# Sheet1.net
KiCad netlist of a schematic drawn in Altium Designer
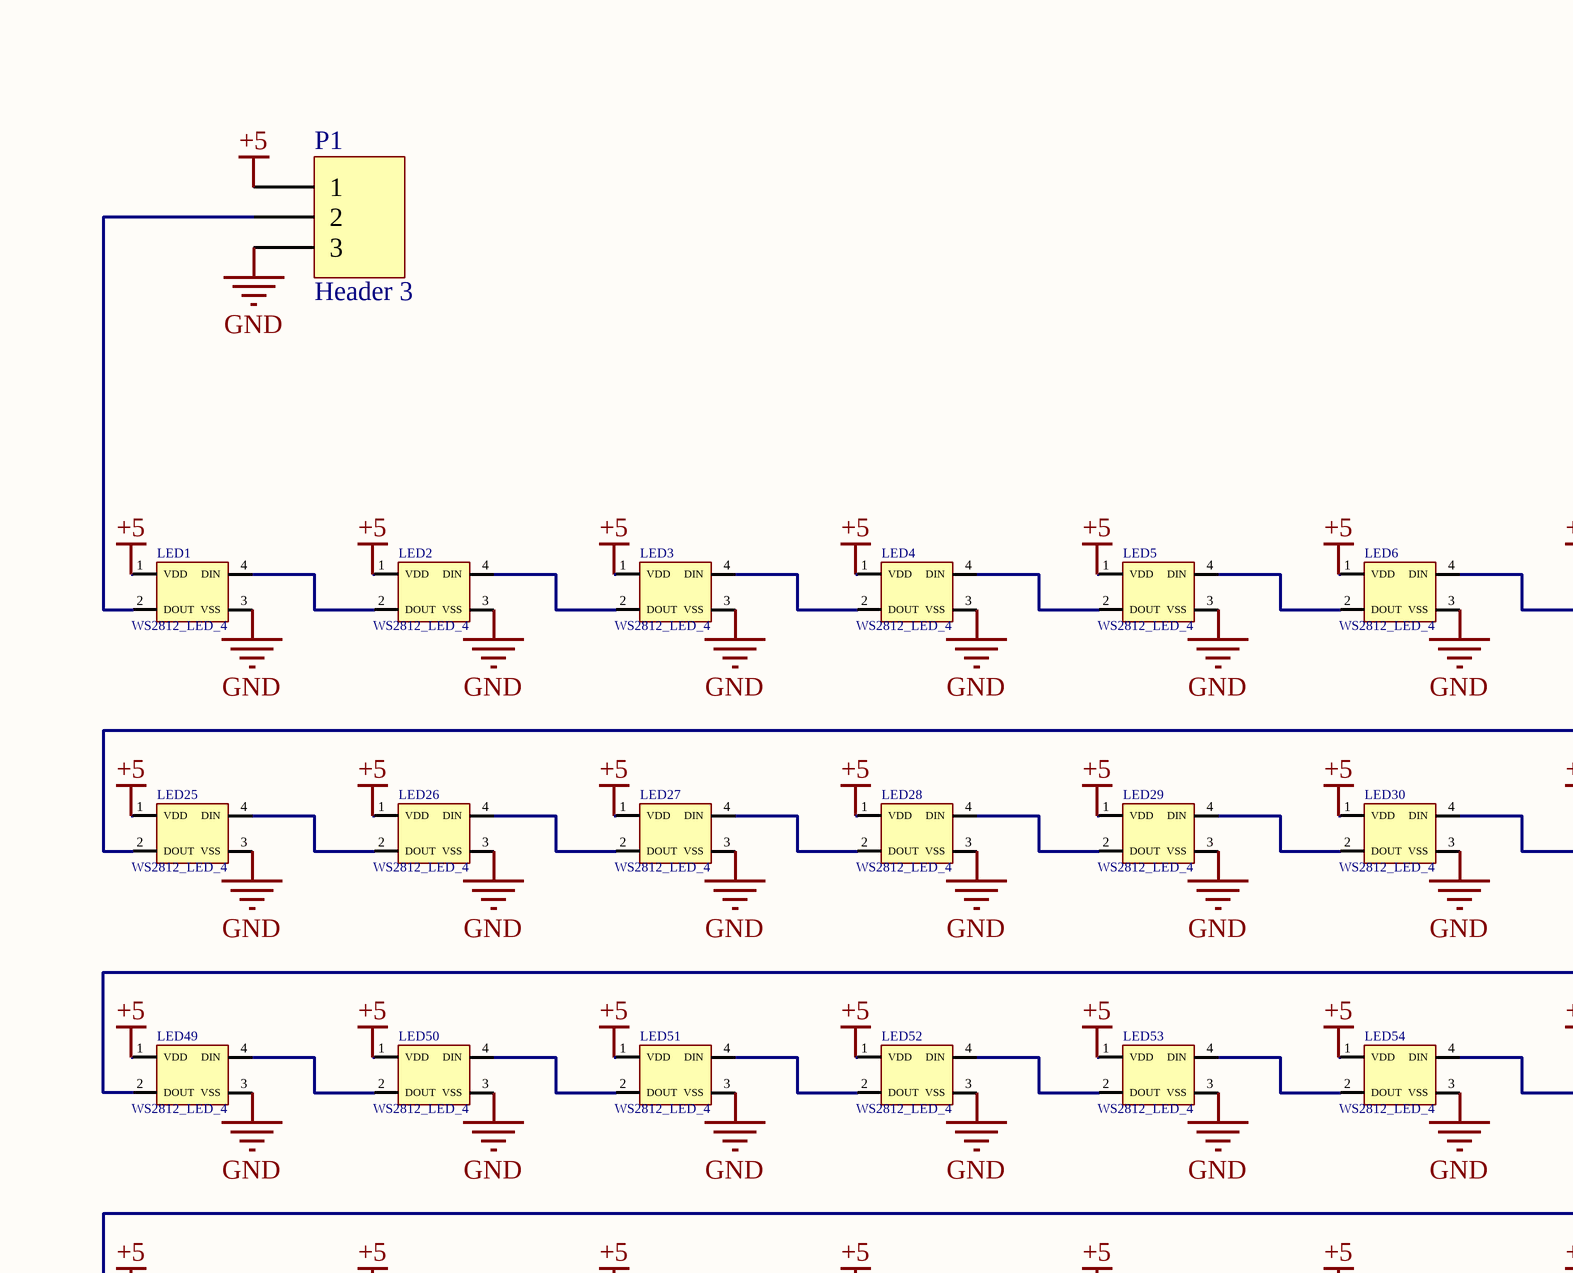
[diagram p0: Sheet1.SchDoc, top column 1 of 4]
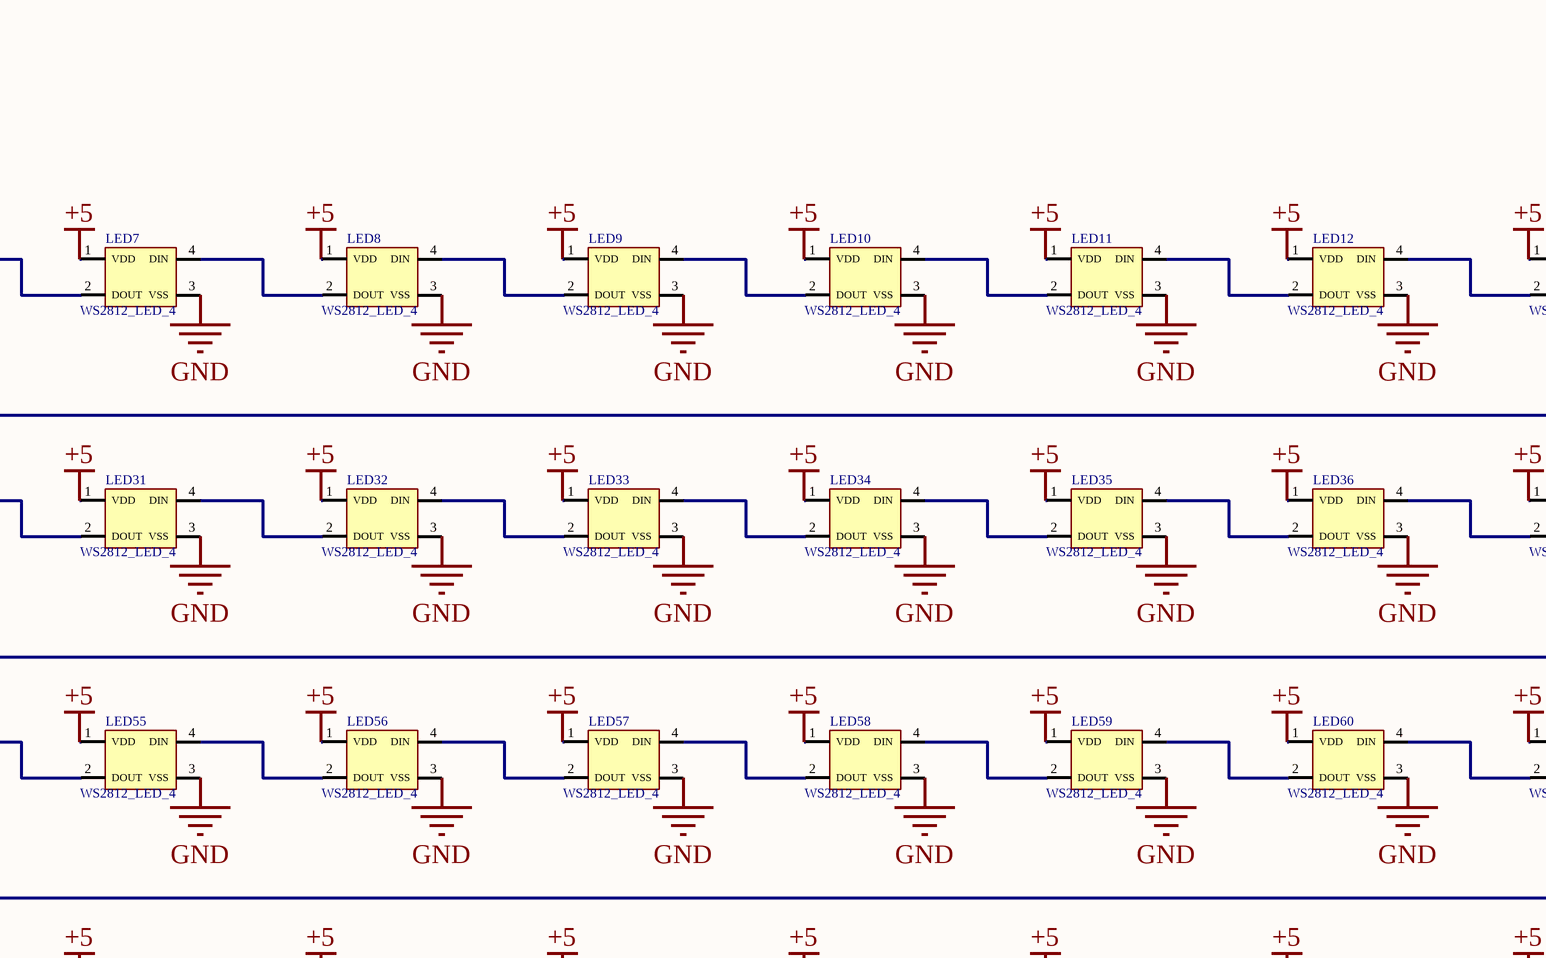
[diagram p1: Sheet1.SchDoc, top column 2 of 4]
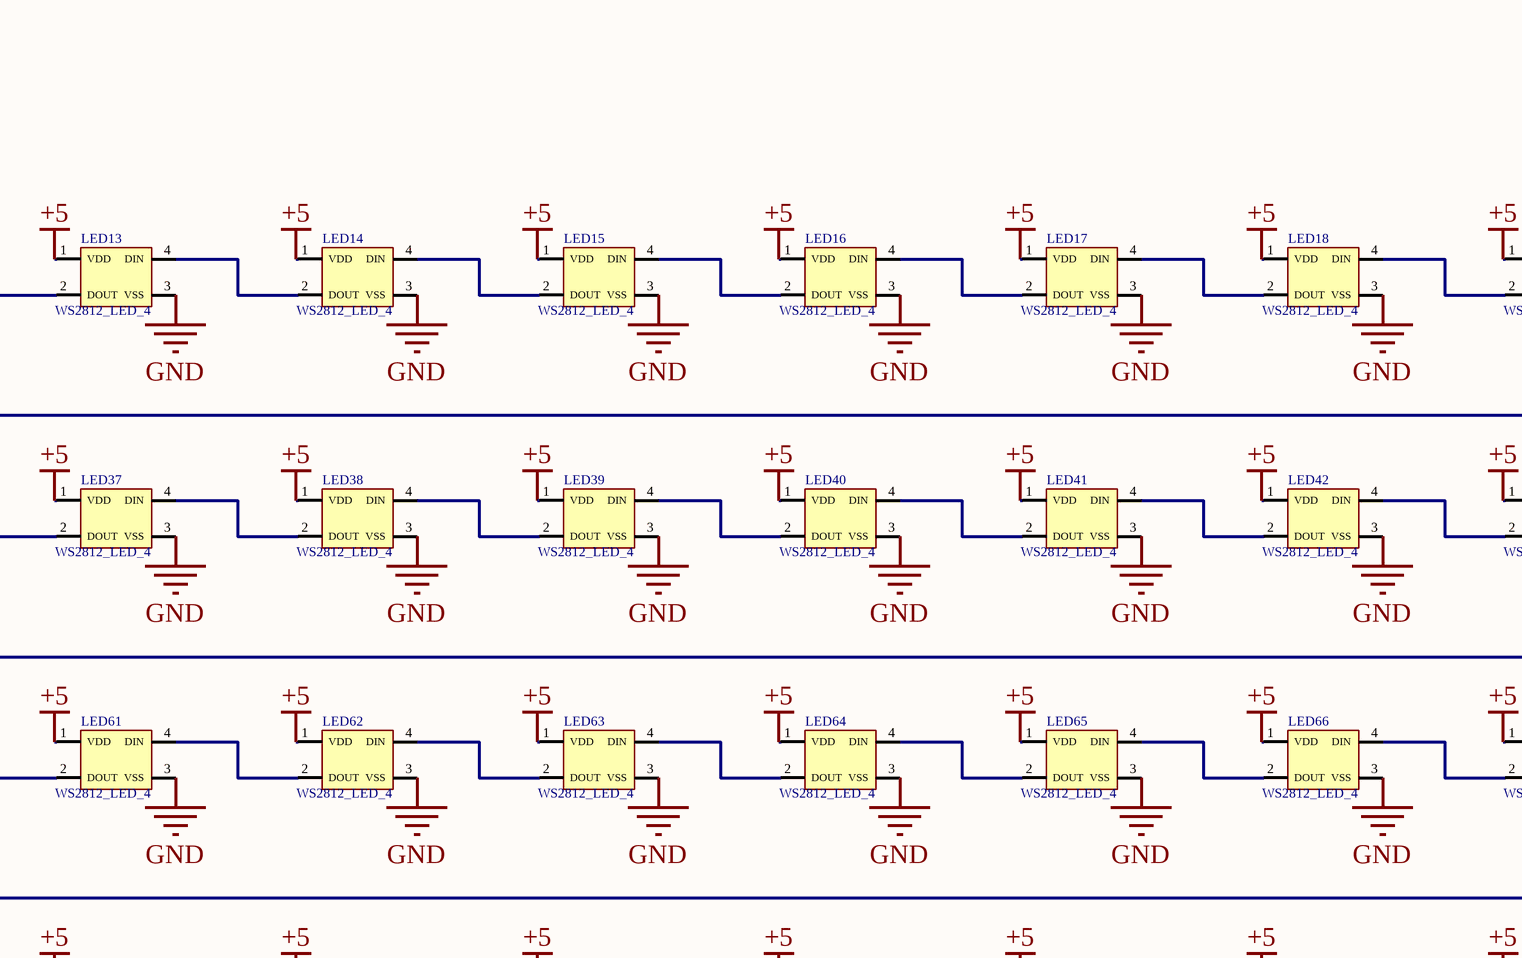
[diagram p2: Sheet1.SchDoc, top column 3 of 4]
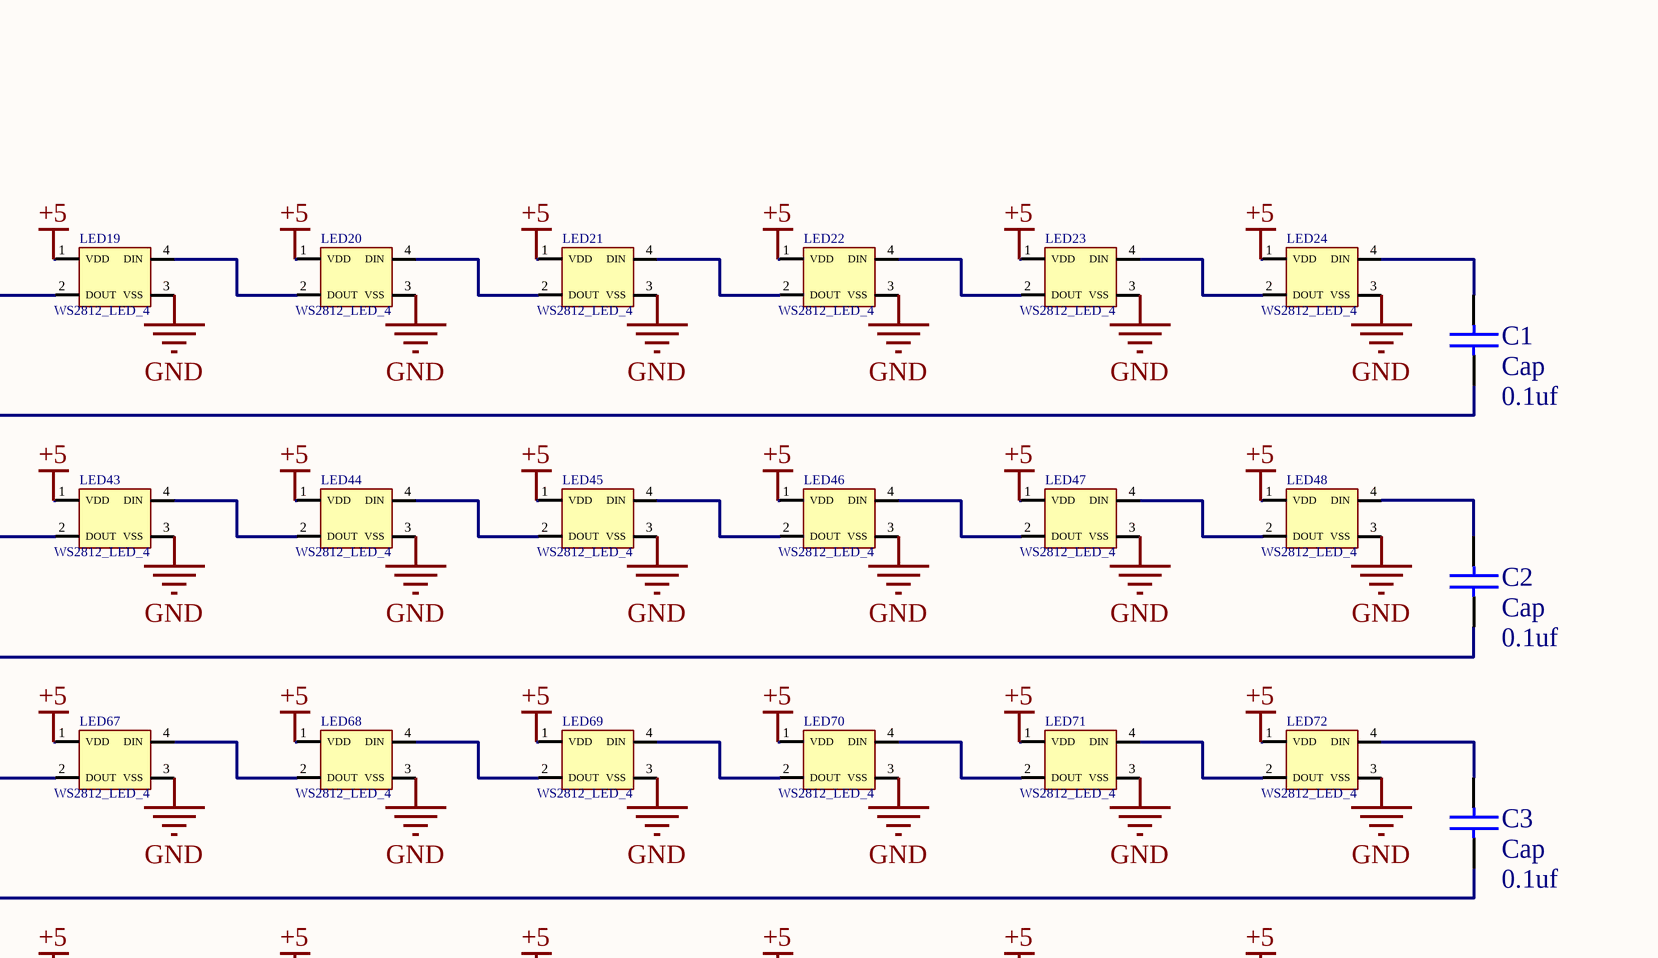
[diagram p3: Sheet1.SchDoc, top column 4 of 4]
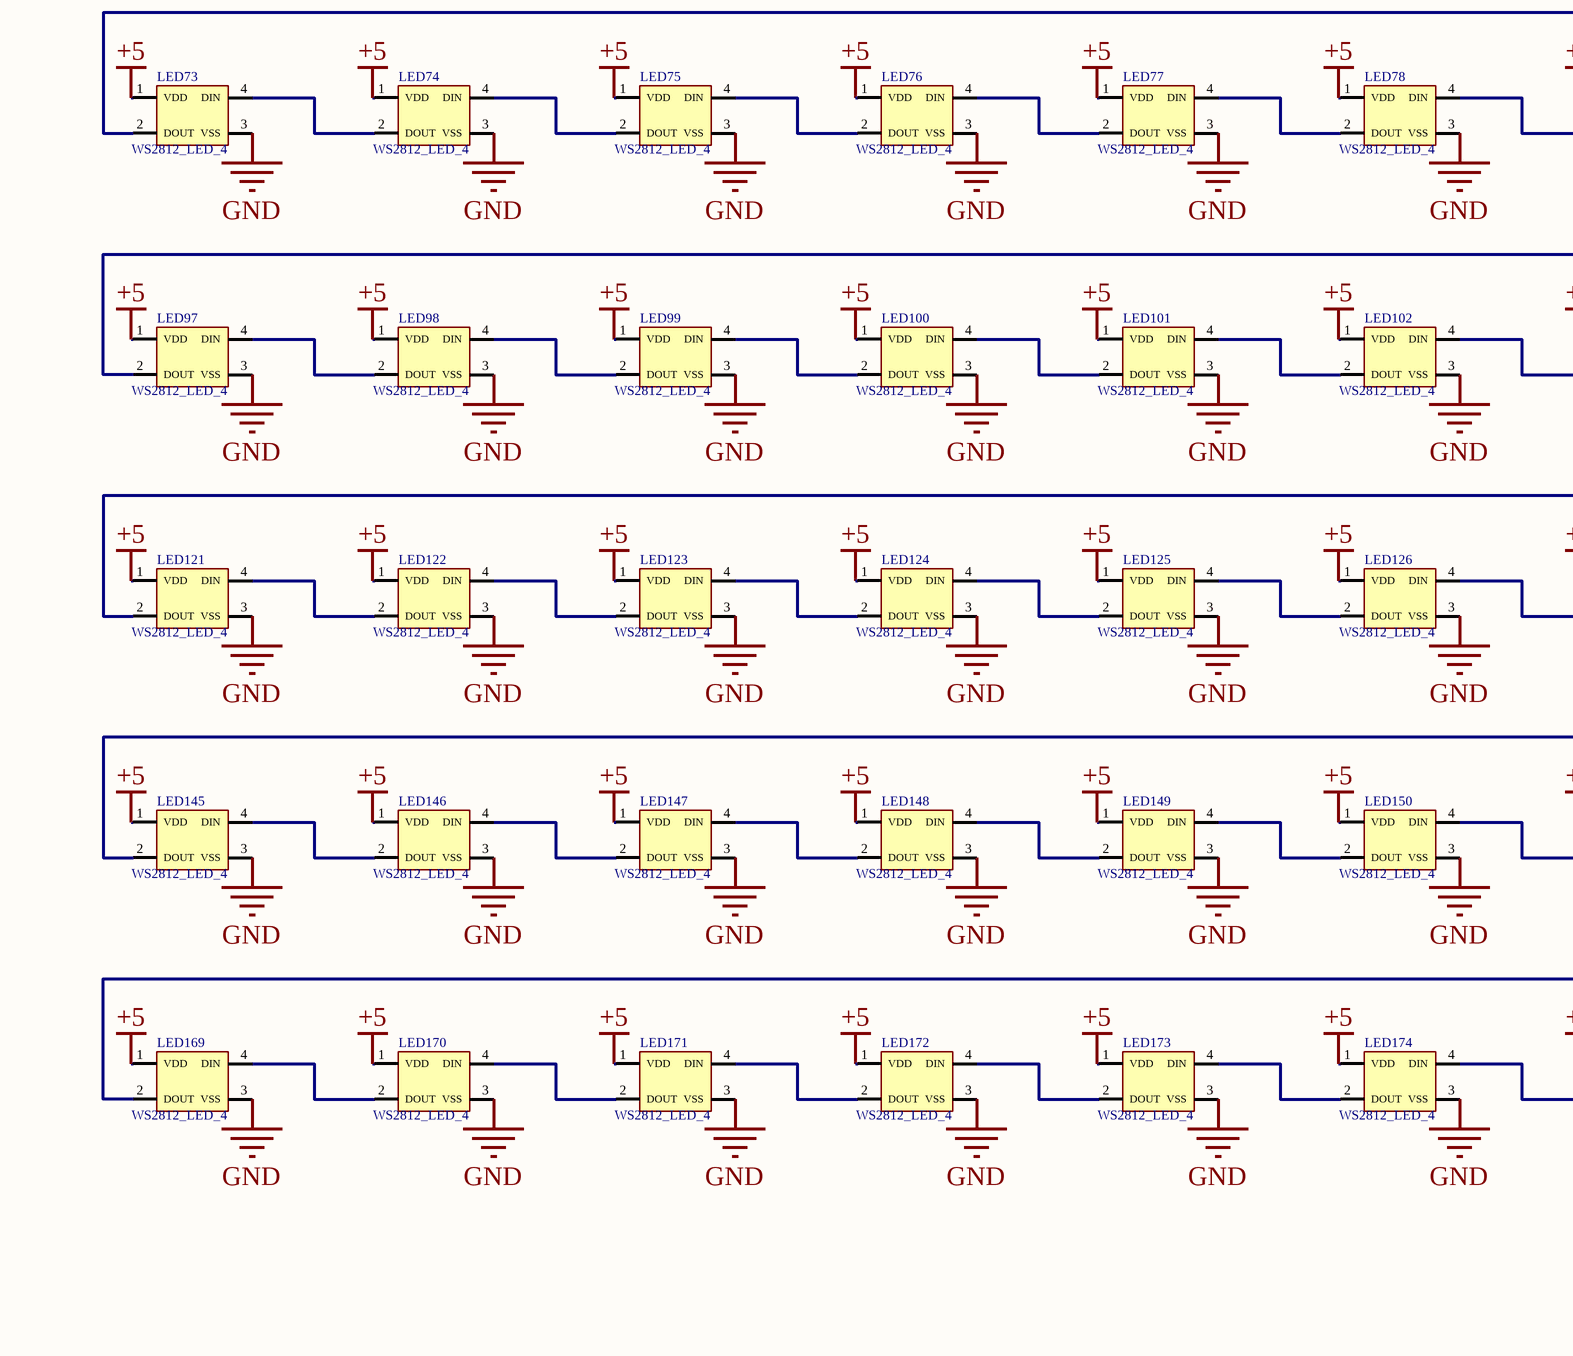
[diagram p4: Sheet1.SchDoc, bottom column 1 of 4]
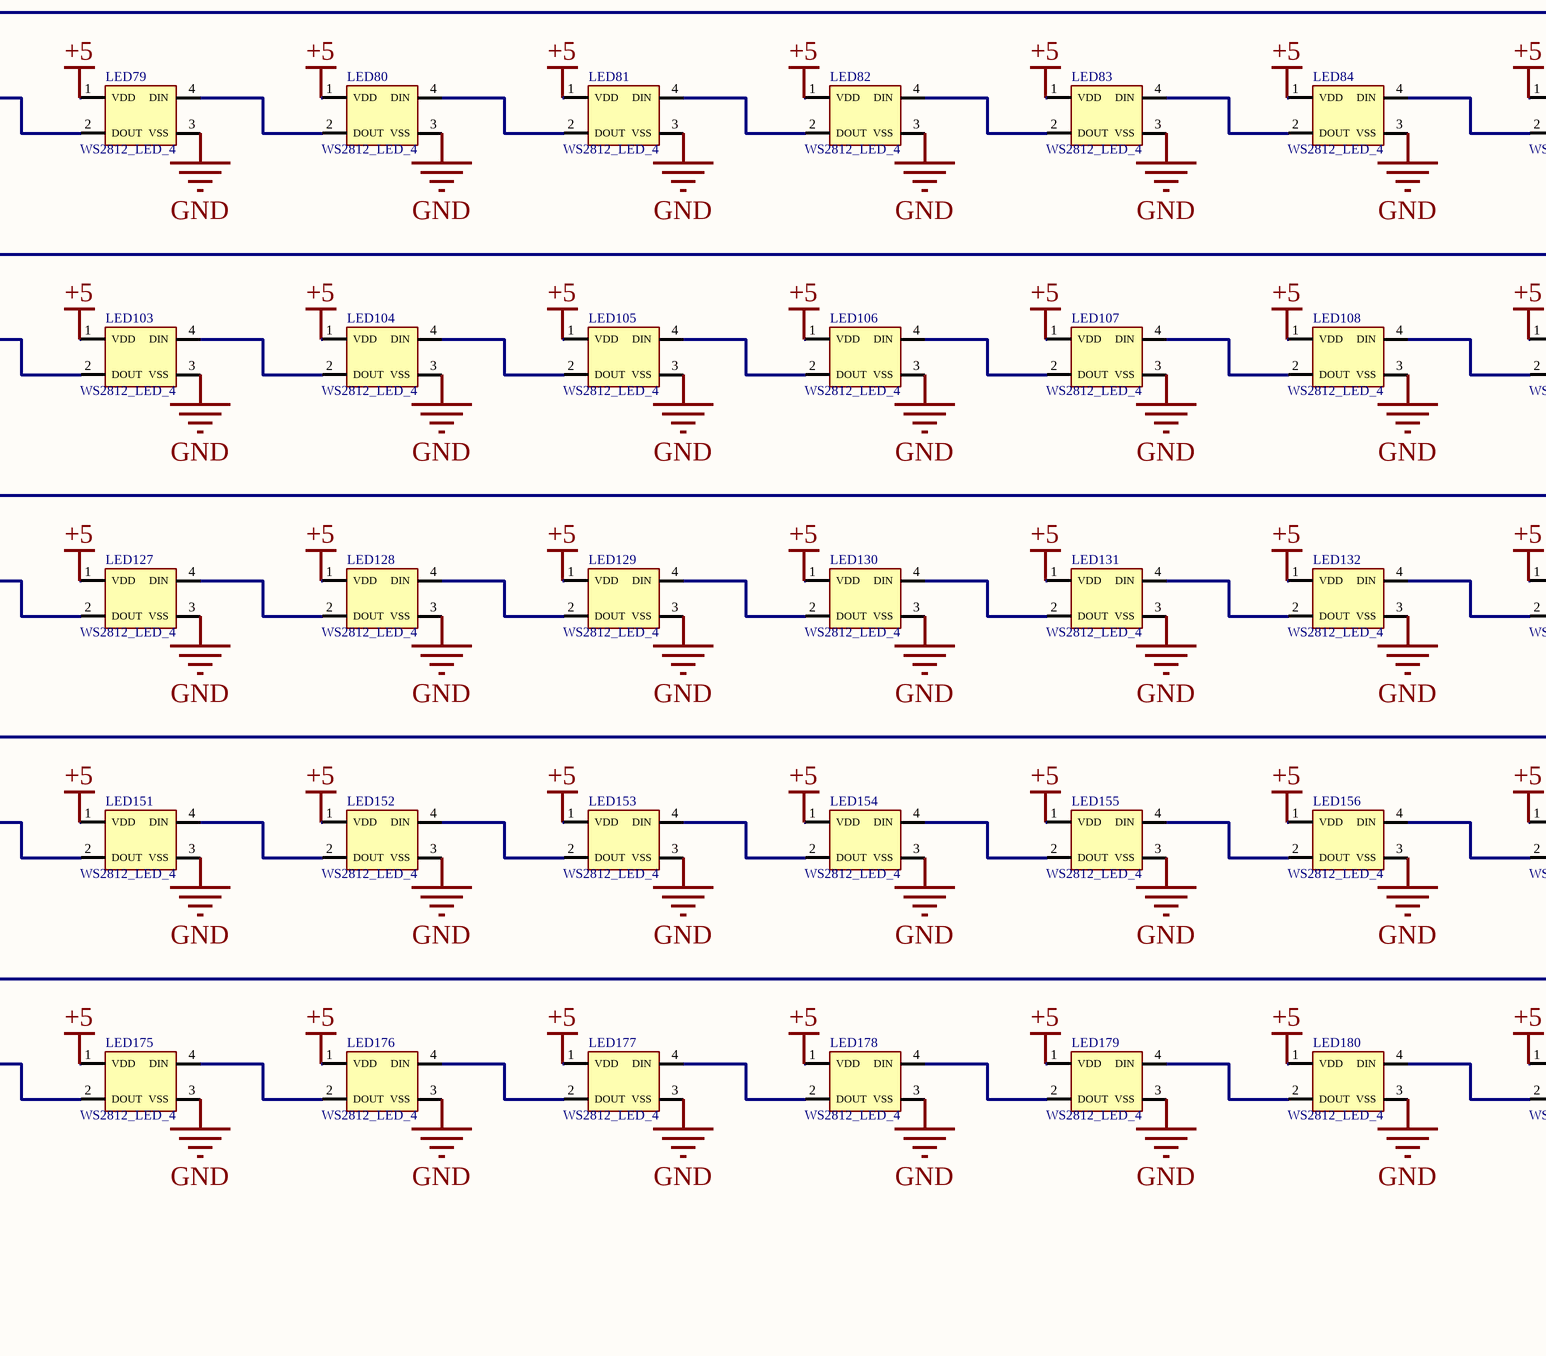
[diagram p5: Sheet1.SchDoc, bottom column 2 of 4]
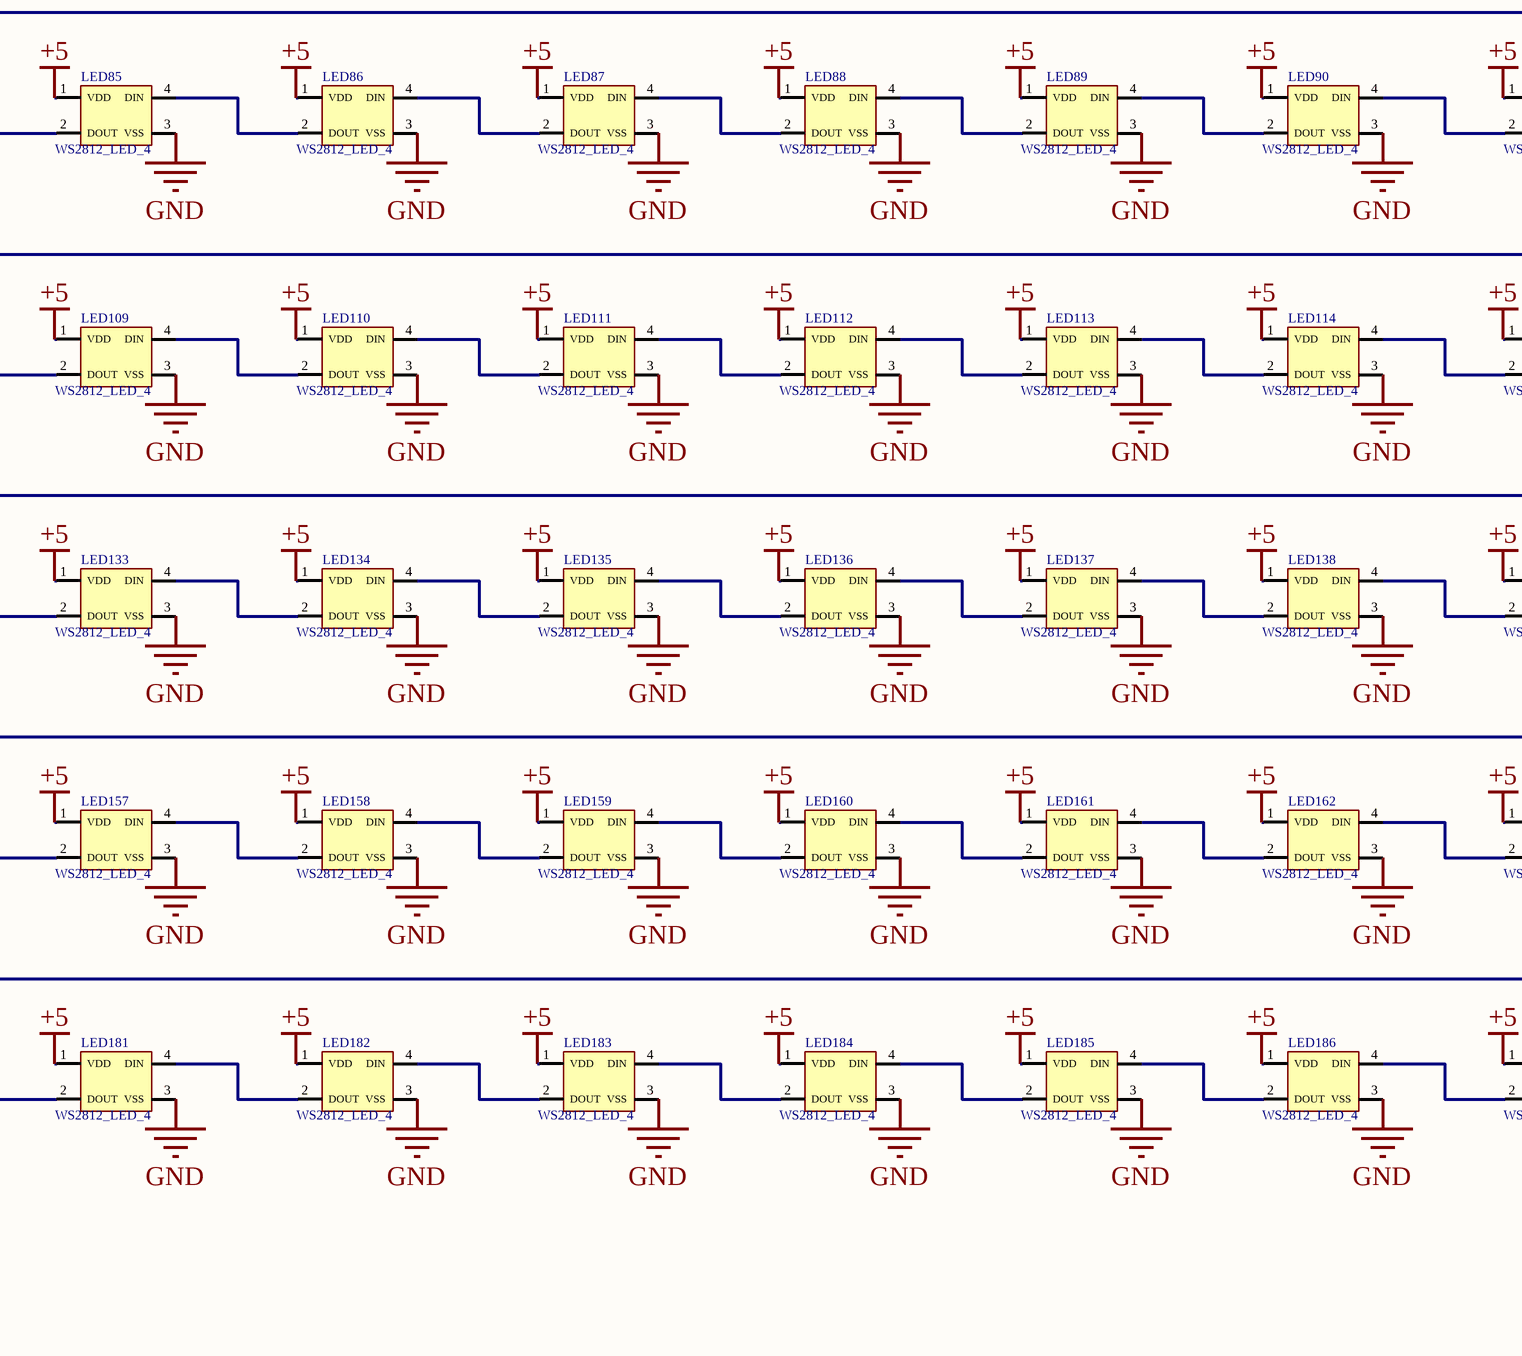
[diagram p6: Sheet1.SchDoc, bottom column 3 of 4]
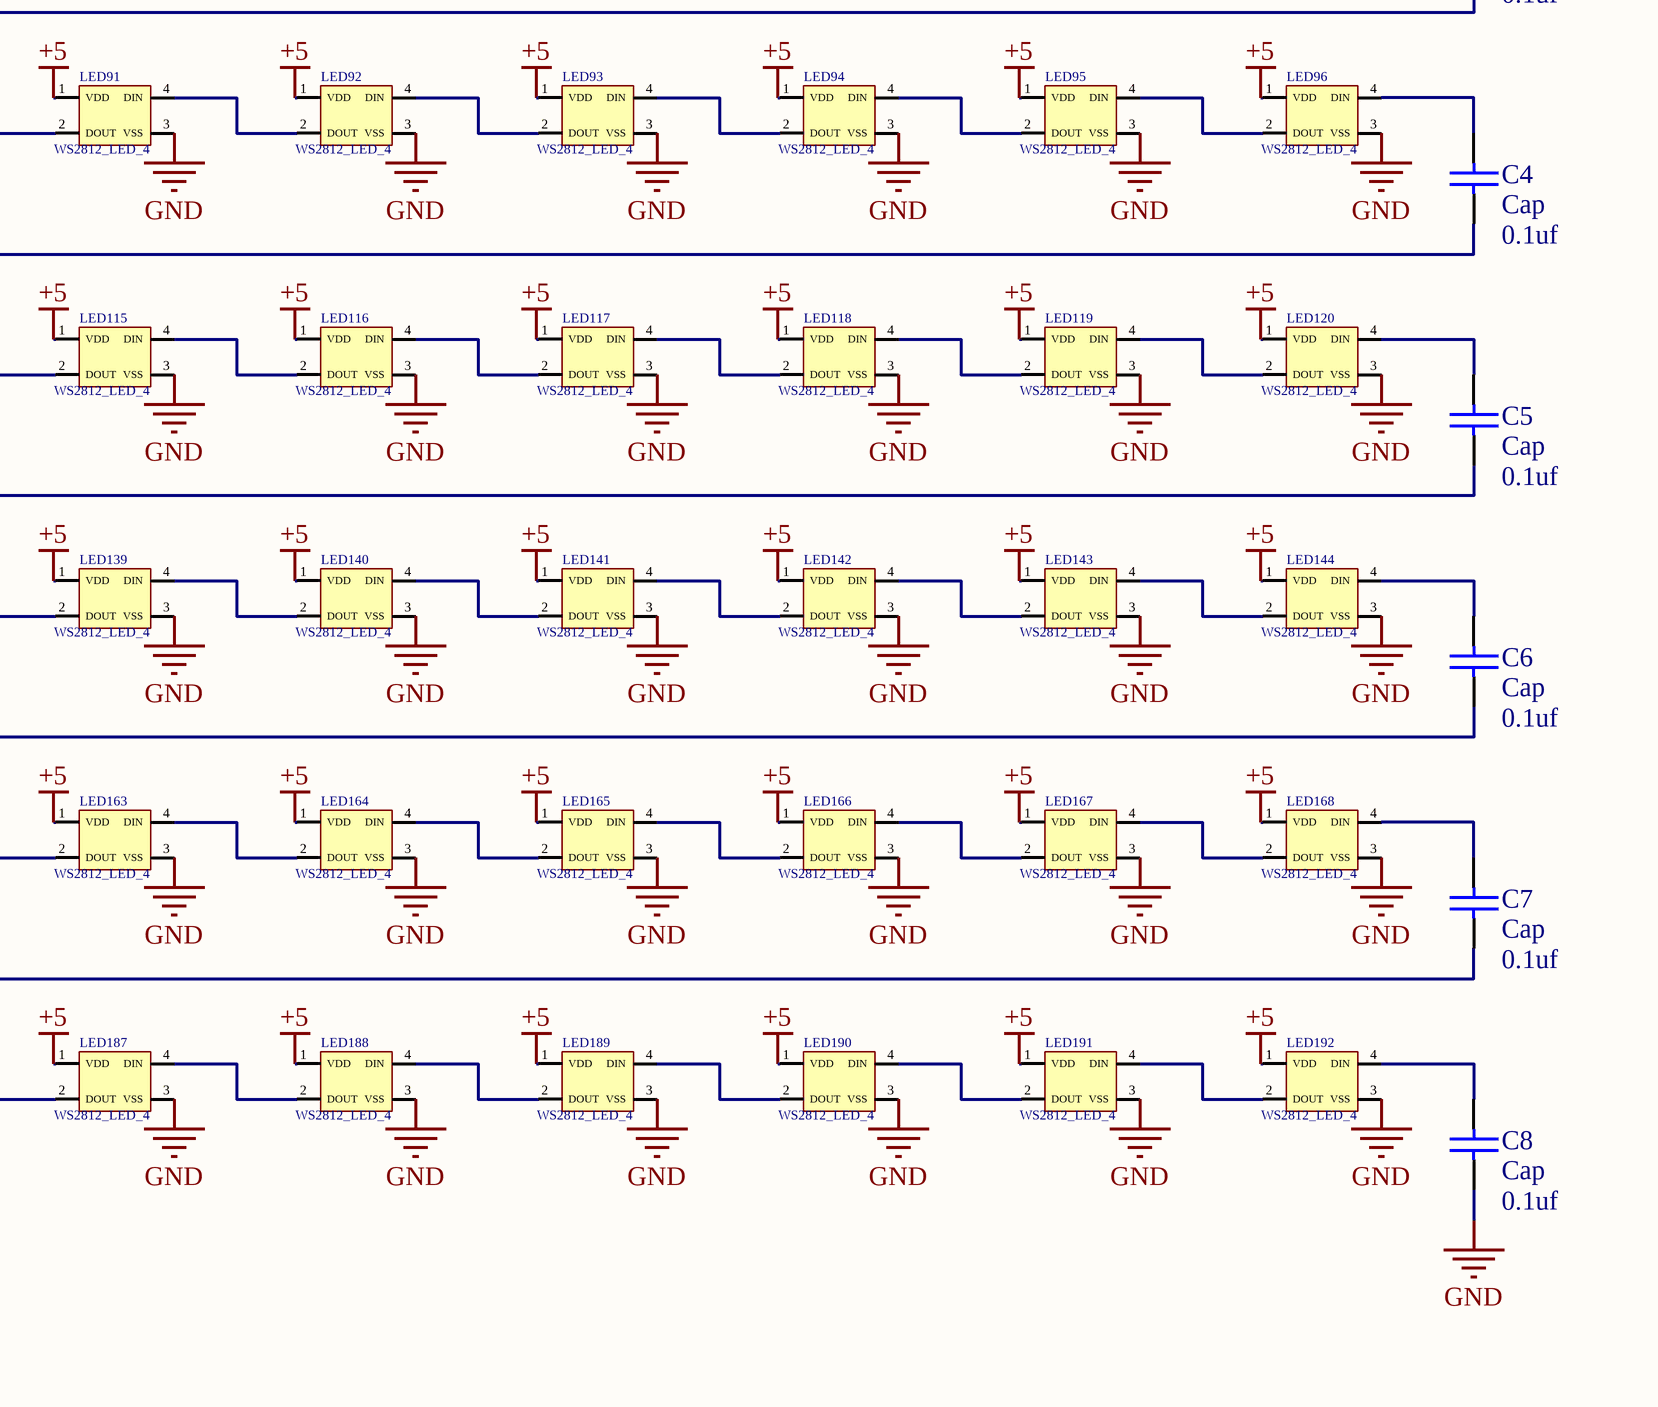
[diagram p7: Sheet1.SchDoc, bottom column 4 of 4]

(export (version "E")
  (design (tool "Eeschema 10.0.6"))
  (components
    (comp (ref "C1")
      (value "Cap")
      (footprint "RAD-0.3")
      (description "Capacitor")
      (fields (field (name "ALTIUM_VALUE") "0.1uf") (field (name "PUBLISHER") "Altium Limited"))
      (libsource (lib "Miscellaneous Devices") (part "Cap"))
    )
    (comp (ref "C2")
      (value "Cap")
      (footprint "RAD-0.3")
      (description "Capacitor")
      (fields (field (name "ALTIUM_VALUE") "0.1uf") (field (name "PUBLISHER") "Altium Limited"))
      (libsource (lib "Miscellaneous Devices") (part "Cap"))
    )
    (comp (ref "C3")
      (value "Cap")
      (footprint "RAD-0.3")
      (description "Capacitor")
      (fields (field (name "ALTIUM_VALUE") "0.1uf") (field (name "PUBLISHER") "Altium Limited"))
      (libsource (lib "Miscellaneous Devices") (part "Cap"))
    )
    (comp (ref "C4")
      (value "Cap")
      (footprint "RAD-0.3")
      (description "Capacitor")
      (fields (field (name "ALTIUM_VALUE") "0.1uf") (field (name "PUBLISHER") "Altium Limited"))
      (libsource (lib "Miscellaneous Devices") (part "Cap"))
    )
    (comp (ref "C5")
      (value "Cap")
      (footprint "RAD-0.3")
      (description "Capacitor")
      (fields (field (name "ALTIUM_VALUE") "0.1uf") (field (name "PUBLISHER") "Altium Limited"))
      (libsource (lib "Miscellaneous Devices") (part "Cap"))
    )
    (comp (ref "C6")
      (value "Cap")
      (footprint "RAD-0.3")
      (description "Capacitor")
      (fields (field (name "ALTIUM_VALUE") "0.1uf") (field (name "PUBLISHER") "Altium Limited"))
      (libsource (lib "Miscellaneous Devices") (part "Cap"))
    )
    (comp (ref "C7")
      (value "Cap")
      (footprint "RAD-0.3")
      (description "Capacitor")
      (fields (field (name "ALTIUM_VALUE") "0.1uf") (field (name "PUBLISHER") "Altium Limited"))
      (libsource (lib "Miscellaneous Devices") (part "Cap"))
    )
    (comp (ref "C8")
      (value "Cap")
      (footprint "RAD-0.3")
      (description "Capacitor")
      (fields (field (name "ALTIUM_VALUE") "0.1uf") (field (name "PUBLISHER") "Altium Limited"))
      (libsource (lib "Miscellaneous Devices") (part "Cap"))
    )
    (comp (ref "LED1")
      (value "WS2812_LED_4")
      (footprint "WS2812_LED_4")
      (libsource (lib "Schlib1") (part "WS2812_LED_4"))
    )
    (comp (ref "LED2")
      (value "WS2812_LED_4")
      (footprint "WS2812_LED_4")
      (libsource (lib "Schlib1") (part "WS2812_LED_4"))
    )
    (comp (ref "LED3")
      (value "WS2812_LED_4")
      (footprint "WS2812_LED_4")
      (libsource (lib "Schlib1") (part "WS2812_LED_4"))
    )
    (comp (ref "LED4")
      (value "WS2812_LED_4")
      (footprint "WS2812_LED_4")
      (libsource (lib "Schlib1") (part "WS2812_LED_4"))
    )
    (comp (ref "LED5")
      (value "WS2812_LED_4")
      (footprint "WS2812_LED_4")
      (libsource (lib "Schlib1") (part "WS2812_LED_4"))
    )
    (comp (ref "LED6")
      (value "WS2812_LED_4")
      (footprint "WS2812_LED_4")
      (libsource (lib "Schlib1") (part "WS2812_LED_4"))
    )
    (comp (ref "LED7")
      (value "WS2812_LED_4")
      (footprint "WS2812_LED_4")
      (libsource (lib "Schlib1") (part "WS2812_LED_4"))
    )
    (comp (ref "LED8")
      (value "WS2812_LED_4")
      (footprint "WS2812_LED_4")
      (libsource (lib "Schlib1") (part "WS2812_LED_4"))
    )
    (comp (ref "LED9")
      (value "WS2812_LED_4")
      (footprint "WS2812_LED_4")
      (libsource (lib "Schlib1") (part "WS2812_LED_4"))
    )
    (comp (ref "LED10")
      (value "WS2812_LED_4")
      (footprint "WS2812_LED_4")
      (libsource (lib "Schlib1") (part "WS2812_LED_4"))
    )
    (comp (ref "LED11")
      (value "WS2812_LED_4")
      (footprint "WS2812_LED_4")
      (libsource (lib "Schlib1") (part "WS2812_LED_4"))
    )
    (comp (ref "LED12")
      (value "WS2812_LED_4")
      (footprint "WS2812_LED_4")
      (libsource (lib "Schlib1") (part "WS2812_LED_4"))
    )
    (comp (ref "LED13")
      (value "WS2812_LED_4")
      (footprint "WS2812_LED_4")
      (libsource (lib "Schlib1") (part "WS2812_LED_4"))
    )
    (comp (ref "LED14")
      (value "WS2812_LED_4")
      (footprint "WS2812_LED_4")
      (libsource (lib "Schlib1") (part "WS2812_LED_4"))
    )
    (comp (ref "LED15")
      (value "WS2812_LED_4")
      (footprint "WS2812_LED_4")
      (libsource (lib "Schlib1") (part "WS2812_LED_4"))
    )
    (comp (ref "LED16")
      (value "WS2812_LED_4")
      (footprint "WS2812_LED_4")
      (libsource (lib "Schlib1") (part "WS2812_LED_4"))
    )
    (comp (ref "LED17")
      (value "WS2812_LED_4")
      (footprint "WS2812_LED_4")
      (libsource (lib "Schlib1") (part "WS2812_LED_4"))
    )
    (comp (ref "LED18")
      (value "WS2812_LED_4")
      (footprint "WS2812_LED_4")
      (libsource (lib "Schlib1") (part "WS2812_LED_4"))
    )
    (comp (ref "LED19")
      (value "WS2812_LED_4")
      (footprint "WS2812_LED_4")
      (libsource (lib "Schlib1") (part "WS2812_LED_4"))
    )
    (comp (ref "LED20")
      (value "WS2812_LED_4")
      (footprint "WS2812_LED_4")
      (libsource (lib "Schlib1") (part "WS2812_LED_4"))
    )
    (comp (ref "LED21")
      (value "WS2812_LED_4")
      (footprint "WS2812_LED_4")
      (libsource (lib "Schlib1") (part "WS2812_LED_4"))
    )
    (comp (ref "LED22")
      (value "WS2812_LED_4")
      (footprint "WS2812_LED_4")
      (libsource (lib "Schlib1") (part "WS2812_LED_4"))
    )
    (comp (ref "LED23")
      (value "WS2812_LED_4")
      (footprint "WS2812_LED_4")
      (libsource (lib "Schlib1") (part "WS2812_LED_4"))
    )
    (comp (ref "LED24")
      (value "WS2812_LED_4")
      (footprint "WS2812_LED_4")
      (libsource (lib "Schlib1") (part "WS2812_LED_4"))
    )
    (comp (ref "LED25")
      (value "WS2812_LED_4")
      (footprint "WS2812_LED_4")
      (libsource (lib "Schlib1") (part "WS2812_LED_4"))
    )
    (comp (ref "LED26")
      (value "WS2812_LED_4")
      (footprint "WS2812_LED_4")
      (libsource (lib "Schlib1") (part "WS2812_LED_4"))
    )
    (comp (ref "LED27")
      (value "WS2812_LED_4")
      (footprint "WS2812_LED_4")
      (libsource (lib "Schlib1") (part "WS2812_LED_4"))
    )
    (comp (ref "LED28")
      (value "WS2812_LED_4")
      (footprint "WS2812_LED_4")
      (libsource (lib "Schlib1") (part "WS2812_LED_4"))
    )
    (comp (ref "LED29")
      (value "WS2812_LED_4")
      (footprint "WS2812_LED_4")
      (libsource (lib "Schlib1") (part "WS2812_LED_4"))
    )
    (comp (ref "LED30")
      (value "WS2812_LED_4")
      (footprint "WS2812_LED_4")
      (libsource (lib "Schlib1") (part "WS2812_LED_4"))
    )
    (comp (ref "LED31")
      (value "WS2812_LED_4")
      (footprint "WS2812_LED_4")
      (libsource (lib "Schlib1") (part "WS2812_LED_4"))
    )
    (comp (ref "LED32")
      (value "WS2812_LED_4")
      (footprint "WS2812_LED_4")
      (libsource (lib "Schlib1") (part "WS2812_LED_4"))
    )
    (comp (ref "LED33")
      (value "WS2812_LED_4")
      (footprint "WS2812_LED_4")
      (libsource (lib "Schlib1") (part "WS2812_LED_4"))
    )
    (comp (ref "LED34")
      (value "WS2812_LED_4")
      (footprint "WS2812_LED_4")
      (libsource (lib "Schlib1") (part "WS2812_LED_4"))
    )
    (comp (ref "LED35")
      (value "WS2812_LED_4")
      (footprint "WS2812_LED_4")
      (libsource (lib "Schlib1") (part "WS2812_LED_4"))
    )
    (comp (ref "LED36")
      (value "WS2812_LED_4")
      (footprint "WS2812_LED_4")
      (libsource (lib "Schlib1") (part "WS2812_LED_4"))
    )
    (comp (ref "LED37")
      (value "WS2812_LED_4")
      (footprint "WS2812_LED_4")
      (libsource (lib "Schlib1") (part "WS2812_LED_4"))
    )
    (comp (ref "LED38")
      (value "WS2812_LED_4")
      (footprint "WS2812_LED_4")
      (libsource (lib "Schlib1") (part "WS2812_LED_4"))
    )
    (comp (ref "LED39")
      (value "WS2812_LED_4")
      (footprint "WS2812_LED_4")
      (libsource (lib "Schlib1") (part "WS2812_LED_4"))
    )
    (comp (ref "LED40")
      (value "WS2812_LED_4")
      (footprint "WS2812_LED_4")
      (libsource (lib "Schlib1") (part "WS2812_LED_4"))
    )
    (comp (ref "LED41")
      (value "WS2812_LED_4")
      (footprint "WS2812_LED_4")
      (libsource (lib "Schlib1") (part "WS2812_LED_4"))
    )
    (comp (ref "LED42")
      (value "WS2812_LED_4")
      (footprint "WS2812_LED_4")
      (libsource (lib "Schlib1") (part "WS2812_LED_4"))
    )
    (comp (ref "LED43")
      (value "WS2812_LED_4")
      (footprint "WS2812_LED_4")
      (libsource (lib "Schlib1") (part "WS2812_LED_4"))
    )
    (comp (ref "LED44")
      (value "WS2812_LED_4")
      (footprint "WS2812_LED_4")
      (libsource (lib "Schlib1") (part "WS2812_LED_4"))
    )
    (comp (ref "LED45")
      (value "WS2812_LED_4")
      (footprint "WS2812_LED_4")
      (libsource (lib "Schlib1") (part "WS2812_LED_4"))
    )
    (comp (ref "LED46")
      (value "WS2812_LED_4")
      (footprint "WS2812_LED_4")
      (libsource (lib "Schlib1") (part "WS2812_LED_4"))
    )
    (comp (ref "LED47")
      (value "WS2812_LED_4")
      (footprint "WS2812_LED_4")
      (libsource (lib "Schlib1") (part "WS2812_LED_4"))
    )
    (comp (ref "LED48")
      (value "WS2812_LED_4")
      (footprint "WS2812_LED_4")
      (libsource (lib "Schlib1") (part "WS2812_LED_4"))
    )
    (comp (ref "LED49")
      (value "WS2812_LED_4")
      (footprint "WS2812_LED_4")
      (libsource (lib "Schlib1") (part "WS2812_LED_4"))
    )
    (comp (ref "LED50")
      (value "WS2812_LED_4")
      (footprint "WS2812_LED_4")
      (libsource (lib "Schlib1") (part "WS2812_LED_4"))
    )
    (comp (ref "LED51")
      (value "WS2812_LED_4")
      (footprint "WS2812_LED_4")
      (libsource (lib "Schlib1") (part "WS2812_LED_4"))
    )
    (comp (ref "LED52")
      (value "WS2812_LED_4")
      (footprint "WS2812_LED_4")
      (libsource (lib "Schlib1") (part "WS2812_LED_4"))
    )
    (comp (ref "LED53")
      (value "WS2812_LED_4")
      (footprint "WS2812_LED_4")
      (libsource (lib "Schlib1") (part "WS2812_LED_4"))
    )
    (comp (ref "LED54")
      (value "WS2812_LED_4")
      (footprint "WS2812_LED_4")
      (libsource (lib "Schlib1") (part "WS2812_LED_4"))
    )
    (comp (ref "LED55")
      (value "WS2812_LED_4")
      (footprint "WS2812_LED_4")
      (libsource (lib "Schlib1") (part "WS2812_LED_4"))
    )
    (comp (ref "LED56")
      (value "WS2812_LED_4")
      (footprint "WS2812_LED_4")
      (libsource (lib "Schlib1") (part "WS2812_LED_4"))
    )
    (comp (ref "LED57")
      (value "WS2812_LED_4")
      (footprint "WS2812_LED_4")
      (libsource (lib "Schlib1") (part "WS2812_LED_4"))
    )
    (comp (ref "LED58")
      (value "WS2812_LED_4")
      (footprint "WS2812_LED_4")
      (libsource (lib "Schlib1") (part "WS2812_LED_4"))
    )
    (comp (ref "LED59")
      (value "WS2812_LED_4")
      (footprint "WS2812_LED_4")
      (libsource (lib "Schlib1") (part "WS2812_LED_4"))
    )
    (comp (ref "LED60")
      (value "WS2812_LED_4")
      (footprint "WS2812_LED_4")
      (libsource (lib "Schlib1") (part "WS2812_LED_4"))
    )
    (comp (ref "LED61")
      (value "WS2812_LED_4")
      (footprint "WS2812_LED_4")
      (libsource (lib "Schlib1") (part "WS2812_LED_4"))
    )
    (comp (ref "LED62")
      (value "WS2812_LED_4")
      (footprint "WS2812_LED_4")
      (libsource (lib "Schlib1") (part "WS2812_LED_4"))
    )
    (comp (ref "LED63")
      (value "WS2812_LED_4")
      (footprint "WS2812_LED_4")
      (libsource (lib "Schlib1") (part "WS2812_LED_4"))
    )
    (comp (ref "LED64")
      (value "WS2812_LED_4")
      (footprint "WS2812_LED_4")
      (libsource (lib "Schlib1") (part "WS2812_LED_4"))
    )
    (comp (ref "LED65")
      (value "WS2812_LED_4")
      (footprint "WS2812_LED_4")
      (libsource (lib "Schlib1") (part "WS2812_LED_4"))
    )
    (comp (ref "LED66")
      (value "WS2812_LED_4")
      (footprint "WS2812_LED_4")
      (libsource (lib "Schlib1") (part "WS2812_LED_4"))
    )
    (comp (ref "LED67")
      (value "WS2812_LED_4")
      (footprint "WS2812_LED_4")
      (libsource (lib "Schlib1") (part "WS2812_LED_4"))
    )
    (comp (ref "LED68")
      (value "WS2812_LED_4")
      (footprint "WS2812_LED_4")
      (libsource (lib "Schlib1") (part "WS2812_LED_4"))
    )
    (comp (ref "LED69")
      (value "WS2812_LED_4")
      (footprint "WS2812_LED_4")
      (libsource (lib "Schlib1") (part "WS2812_LED_4"))
    )
    (comp (ref "LED70")
      (value "WS2812_LED_4")
      (footprint "WS2812_LED_4")
      (libsource (lib "Schlib1") (part "WS2812_LED_4"))
    )
    (comp (ref "LED71")
      (value "WS2812_LED_4")
      (footprint "WS2812_LED_4")
      (libsource (lib "Schlib1") (part "WS2812_LED_4"))
    )
    (comp (ref "LED72")
      (value "WS2812_LED_4")
      (footprint "WS2812_LED_4")
      (libsource (lib "Schlib1") (part "WS2812_LED_4"))
    )
    (comp (ref "LED73")
      (value "WS2812_LED_4")
      (footprint "WS2812_LED_4")
      (libsource (lib "Schlib1") (part "WS2812_LED_4"))
    )
    (comp (ref "LED74")
      (value "WS2812_LED_4")
      (footprint "WS2812_LED_4")
      (libsource (lib "Schlib1") (part "WS2812_LED_4"))
    )
    (comp (ref "LED75")
      (value "WS2812_LED_4")
      (footprint "WS2812_LED_4")
      (libsource (lib "Schlib1") (part "WS2812_LED_4"))
    )
    (comp (ref "LED76")
      (value "WS2812_LED_4")
      (footprint "WS2812_LED_4")
      (libsource (lib "Schlib1") (part "WS2812_LED_4"))
    )
    (comp (ref "LED77")
      (value "WS2812_LED_4")
      (footprint "WS2812_LED_4")
      (libsource (lib "Schlib1") (part "WS2812_LED_4"))
    )
    (comp (ref "LED78")
      (value "WS2812_LED_4")
      (footprint "WS2812_LED_4")
      (libsource (lib "Schlib1") (part "WS2812_LED_4"))
    )
    (comp (ref "LED79")
      (value "WS2812_LED_4")
      (footprint "WS2812_LED_4")
      (libsource (lib "Schlib1") (part "WS2812_LED_4"))
    )
    (comp (ref "LED80")
      (value "WS2812_LED_4")
      (footprint "WS2812_LED_4")
      (libsource (lib "Schlib1") (part "WS2812_LED_4"))
    )
    (comp (ref "LED81")
      (value "WS2812_LED_4")
      (footprint "WS2812_LED_4")
      (libsource (lib "Schlib1") (part "WS2812_LED_4"))
    )
    (comp (ref "LED82")
      (value "WS2812_LED_4")
      (footprint "WS2812_LED_4")
      (libsource (lib "Schlib1") (part "WS2812_LED_4"))
    )
    (comp (ref "LED83")
      (value "WS2812_LED_4")
      (footprint "WS2812_LED_4")
      (libsource (lib "Schlib1") (part "WS2812_LED_4"))
    )
    (comp (ref "LED84")
      (value "WS2812_LED_4")
      (footprint "WS2812_LED_4")
      (libsource (lib "Schlib1") (part "WS2812_LED_4"))
    )
    (comp (ref "LED85")
      (value "WS2812_LED_4")
      (footprint "WS2812_LED_4")
      (libsource (lib "Schlib1") (part "WS2812_LED_4"))
    )
    (comp (ref "LED86")
      (value "WS2812_LED_4")
      (footprint "WS2812_LED_4")
      (libsource (lib "Schlib1") (part "WS2812_LED_4"))
    )
    (comp (ref "LED87")
      (value "WS2812_LED_4")
      (footprint "WS2812_LED_4")
      (libsource (lib "Schlib1") (part "WS2812_LED_4"))
    )
    (comp (ref "LED88")
      (value "WS2812_LED_4")
      (footprint "WS2812_LED_4")
      (libsource (lib "Schlib1") (part "WS2812_LED_4"))
    )
    (comp (ref "LED89")
      (value "WS2812_LED_4")
      (footprint "WS2812_LED_4")
      (libsource (lib "Schlib1") (part "WS2812_LED_4"))
    )
    (comp (ref "LED90")
      (value "WS2812_LED_4")
      (footprint "WS2812_LED_4")
      (libsource (lib "Schlib1") (part "WS2812_LED_4"))
    )
    (comp (ref "LED91")
      (value "WS2812_LED_4")
      (footprint "WS2812_LED_4")
      (libsource (lib "Schlib1") (part "WS2812_LED_4"))
    )
    (comp (ref "LED92")
      (value "WS2812_LED_4")
      (footprint "WS2812_LED_4")
      (libsource (lib "Schlib1") (part "WS2812_LED_4"))
    )
    (comp (ref "LED93")
      (value "WS2812_LED_4")
      (footprint "WS2812_LED_4")
      (libsource (lib "Schlib1") (part "WS2812_LED_4"))
    )
    (comp (ref "LED94")
      (value "WS2812_LED_4")
      (footprint "WS2812_LED_4")
      (libsource (lib "Schlib1") (part "WS2812_LED_4"))
    )
    (comp (ref "LED95")
      (value "WS2812_LED_4")
      (footprint "WS2812_LED_4")
      (libsource (lib "Schlib1") (part "WS2812_LED_4"))
    )
    (comp (ref "LED96")
      (value "WS2812_LED_4")
      (footprint "WS2812_LED_4")
      (libsource (lib "Schlib1") (part "WS2812_LED_4"))
    )
    (comp (ref "LED97")
      (value "WS2812_LED_4")
      (footprint "WS2812_LED_4")
      (libsource (lib "Schlib1") (part "WS2812_LED_4"))
    )
    (comp (ref "LED98")
      (value "WS2812_LED_4")
      (footprint "WS2812_LED_4")
      (libsource (lib "Schlib1") (part "WS2812_LED_4"))
    )
    (comp (ref "LED99")
      (value "WS2812_LED_4")
      (footprint "WS2812_LED_4")
      (libsource (lib "Schlib1") (part "WS2812_LED_4"))
    )
    (comp (ref "LED100")
      (value "WS2812_LED_4")
      (footprint "WS2812_LED_4")
      (libsource (lib "Schlib1") (part "WS2812_LED_4"))
    )
    (comp (ref "LED101")
      (value "WS2812_LED_4")
      (footprint "WS2812_LED_4")
      (libsource (lib "Schlib1") (part "WS2812_LED_4"))
    )
    (comp (ref "LED102")
      (value "WS2812_LED_4")
      (footprint "WS2812_LED_4")
      (libsource (lib "Schlib1") (part "WS2812_LED_4"))
    )
    (comp (ref "LED103")
      (value "WS2812_LED_4")
      (footprint "WS2812_LED_4")
      (libsource (lib "Schlib1") (part "WS2812_LED_4"))
    )
    (comp (ref "LED104")
      (value "WS2812_LED_4")
      (footprint "WS2812_LED_4")
      (libsource (lib "Schlib1") (part "WS2812_LED_4"))
    )
    (comp (ref "LED105")
      (value "WS2812_LED_4")
      (footprint "WS2812_LED_4")
      (libsource (lib "Schlib1") (part "WS2812_LED_4"))
    )
    (comp (ref "LED106")
      (value "WS2812_LED_4")
      (footprint "WS2812_LED_4")
      (libsource (lib "Schlib1") (part "WS2812_LED_4"))
    )
    (comp (ref "LED107")
      (value "WS2812_LED_4")
      (footprint "WS2812_LED_4")
      (libsource (lib "Schlib1") (part "WS2812_LED_4"))
    )
    (comp (ref "LED108")
      (value "WS2812_LED_4")
      (footprint "WS2812_LED_4")
      (libsource (lib "Schlib1") (part "WS2812_LED_4"))
    )
    (comp (ref "LED109")
      (value "WS2812_LED_4")
      (footprint "WS2812_LED_4")
      (libsource (lib "Schlib1") (part "WS2812_LED_4"))
    )
    (comp (ref "LED110")
      (value "WS2812_LED_4")
      (footprint "WS2812_LED_4")
      (libsource (lib "Schlib1") (part "WS2812_LED_4"))
    )
    (comp (ref "LED111")
      (value "WS2812_LED_4")
      (footprint "WS2812_LED_4")
      (libsource (lib "Schlib1") (part "WS2812_LED_4"))
    )
    (comp (ref "LED112")
      (value "WS2812_LED_4")
      (footprint "WS2812_LED_4")
      (libsource (lib "Schlib1") (part "WS2812_LED_4"))
    )
    (comp (ref "LED113")
      (value "WS2812_LED_4")
      (footprint "WS2812_LED_4")
      (libsource (lib "Schlib1") (part "WS2812_LED_4"))
    )
    (comp (ref "LED114")
      (value "WS2812_LED_4")
      (footprint "WS2812_LED_4")
      (libsource (lib "Schlib1") (part "WS2812_LED_4"))
    )
    (comp (ref "LED115")
      (value "WS2812_LED_4")
      (footprint "WS2812_LED_4")
      (libsource (lib "Schlib1") (part "WS2812_LED_4"))
    )
    (comp (ref "LED116")
      (value "WS2812_LED_4")
      (footprint "WS2812_LED_4")
      (libsource (lib "Schlib1") (part "WS2812_LED_4"))
    )
    (comp (ref "LED117")
      (value "WS2812_LED_4")
      (footprint "WS2812_LED_4")
      (libsource (lib "Schlib1") (part "WS2812_LED_4"))
    )
    (comp (ref "LED118")
      (value "WS2812_LED_4")
      (footprint "WS2812_LED_4")
      (libsource (lib "Schlib1") (part "WS2812_LED_4"))
    )
    (comp (ref "LED119")
      (value "WS2812_LED_4")
      (footprint "WS2812_LED_4")
      (libsource (lib "Schlib1") (part "WS2812_LED_4"))
    )
    (comp (ref "LED120")
      (value "WS2812_LED_4")
      (footprint "WS2812_LED_4")
      (libsource (lib "Schlib1") (part "WS2812_LED_4"))
    )
    (comp (ref "LED121")
      (value "WS2812_LED_4")
      (footprint "WS2812_LED_4")
      (libsource (lib "Schlib1") (part "WS2812_LED_4"))
    )
    (comp (ref "LED122")
      (value "WS2812_LED_4")
      (footprint "WS2812_LED_4")
      (libsource (lib "Schlib1") (part "WS2812_LED_4"))
    )
    (comp (ref "LED123")
      (value "WS2812_LED_4")
      (footprint "WS2812_LED_4")
      (libsource (lib "Schlib1") (part "WS2812_LED_4"))
    )
    (comp (ref "LED124")
      (value "WS2812_LED_4")
      (footprint "WS2812_LED_4")
      (libsource (lib "Schlib1") (part "WS2812_LED_4"))
    )
    (comp (ref "LED125")
      (value "WS2812_LED_4")
      (footprint "WS2812_LED_4")
      (libsource (lib "Schlib1") (part "WS2812_LED_4"))
    )
    (comp (ref "LED126")
      (value "WS2812_LED_4")
      (footprint "WS2812_LED_4")
      (libsource (lib "Schlib1") (part "WS2812_LED_4"))
    )
    (comp (ref "LED127")
      (value "WS2812_LED_4")
      (footprint "WS2812_LED_4")
      (libsource (lib "Schlib1") (part "WS2812_LED_4"))
    )
    (comp (ref "LED128")
      (value "WS2812_LED_4")
      (footprint "WS2812_LED_4")
      (libsource (lib "Schlib1") (part "WS2812_LED_4"))
    )
    (comp (ref "LED129")
      (value "WS2812_LED_4")
      (footprint "WS2812_LED_4")
      (libsource (lib "Schlib1") (part "WS2812_LED_4"))
    )
    (comp (ref "LED130")
      (value "WS2812_LED_4")
      (footprint "WS2812_LED_4")
      (libsource (lib "Schlib1") (part "WS2812_LED_4"))
    )
    (comp (ref "LED131")
      (value "WS2812_LED_4")
      (footprint "WS2812_LED_4")
      (libsource (lib "Schlib1") (part "WS2812_LED_4"))
    )
    (comp (ref "LED132")
      (value "WS2812_LED_4")
      (footprint "WS2812_LED_4")
      (libsource (lib "Schlib1") (part "WS2812_LED_4"))
    )
    (comp (ref "LED133")
      (value "WS2812_LED_4")
      (footprint "WS2812_LED_4")
      (libsource (lib "Schlib1") (part "WS2812_LED_4"))
    )
    (comp (ref "LED134")
      (value "WS2812_LED_4")
      (footprint "WS2812_LED_4")
      (libsource (lib "Schlib1") (part "WS2812_LED_4"))
    )
    (comp (ref "LED135")
      (value "WS2812_LED_4")
      (footprint "WS2812_LED_4")
      (libsource (lib "Schlib1") (part "WS2812_LED_4"))
    )
    (comp (ref "LED136")
      (value "WS2812_LED_4")
      (footprint "WS2812_LED_4")
      (libsource (lib "Schlib1") (part "WS2812_LED_4"))
    )
    (comp (ref "LED137")
      (value "WS2812_LED_4")
      (footprint "WS2812_LED_4")
      (libsource (lib "Schlib1") (part "WS2812_LED_4"))
    )
    (comp (ref "LED138")
      (value "WS2812_LED_4")
      (footprint "WS2812_LED_4")
      (libsource (lib "Schlib1") (part "WS2812_LED_4"))
    )
    (comp (ref "LED139")
      (value "WS2812_LED_4")
      (footprint "WS2812_LED_4")
      (libsource (lib "Schlib1") (part "WS2812_LED_4"))
    )
    (comp (ref "LED140")
      (value "WS2812_LED_4")
      (footprint "WS2812_LED_4")
      (libsource (lib "Schlib1") (part "WS2812_LED_4"))
    )
    (comp (ref "LED141")
      (value "WS2812_LED_4")
      (footprint "WS2812_LED_4")
      (libsource (lib "Schlib1") (part "WS2812_LED_4"))
    )
    (comp (ref "LED142")
      (value "WS2812_LED_4")
      (footprint "WS2812_LED_4")
      (libsource (lib "Schlib1") (part "WS2812_LED_4"))
    )
    (comp (ref "LED143")
      (value "WS2812_LED_4")
      (footprint "WS2812_LED_4")
      (libsource (lib "Schlib1") (part "WS2812_LED_4"))
    )
    (comp (ref "LED144")
      (value "WS2812_LED_4")
      (footprint "WS2812_LED_4")
      (libsource (lib "Schlib1") (part "WS2812_LED_4"))
    )
    (comp (ref "LED145")
      (value "WS2812_LED_4")
      (footprint "WS2812_LED_4")
      (libsource (lib "Schlib1") (part "WS2812_LED_4"))
    )
    (comp (ref "LED146")
      (value "WS2812_LED_4")
      (footprint "WS2812_LED_4")
      (libsource (lib "Schlib1") (part "WS2812_LED_4"))
    )
    (comp (ref "LED147")
      (value "WS2812_LED_4")
      (footprint "WS2812_LED_4")
      (libsource (lib "Schlib1") (part "WS2812_LED_4"))
    )
    (comp (ref "LED148")
      (value "WS2812_LED_4")
      (footprint "WS2812_LED_4")
      (libsource (lib "Schlib1") (part "WS2812_LED_4"))
    )
    (comp (ref "LED149")
      (value "WS2812_LED_4")
      (footprint "WS2812_LED_4")
      (libsource (lib "Schlib1") (part "WS2812_LED_4"))
    )
    (comp (ref "LED150")
      (value "WS2812_LED_4")
      (footprint "WS2812_LED_4")
      (libsource (lib "Schlib1") (part "WS2812_LED_4"))
    )
    (comp (ref "LED151")
      (value "WS2812_LED_4")
      (footprint "WS2812_LED_4")
      (libsource (lib "Schlib1") (part "WS2812_LED_4"))
    )
    (comp (ref "LED152")
      (value "WS2812_LED_4")
      (footprint "WS2812_LED_4")
      (libsource (lib "Schlib1") (part "WS2812_LED_4"))
    )
    (comp (ref "LED153")
      (value "WS2812_LED_4")
      (footprint "WS2812_LED_4")
      (libsource (lib "Schlib1") (part "WS2812_LED_4"))
    )
    (comp (ref "LED154")
      (value "WS2812_LED_4")
      (footprint "WS2812_LED_4")
      (libsource (lib "Schlib1") (part "WS2812_LED_4"))
    )
    (comp (ref "LED155")
      (value "WS2812_LED_4")
      (footprint "WS2812_LED_4")
      (libsource (lib "Schlib1") (part "WS2812_LED_4"))
    )
    (comp (ref "LED156")
      (value "WS2812_LED_4")
      (footprint "WS2812_LED_4")
      (libsource (lib "Schlib1") (part "WS2812_LED_4"))
    )
    (comp (ref "LED157")
      (value "WS2812_LED_4")
      (footprint "WS2812_LED_4")
      (libsource (lib "Schlib1") (part "WS2812_LED_4"))
    )
    (comp (ref "LED158")
      (value "WS2812_LED_4")
      (footprint "WS2812_LED_4")
      (libsource (lib "Schlib1") (part "WS2812_LED_4"))
    )
    (comp (ref "LED159")
      (value "WS2812_LED_4")
      (footprint "WS2812_LED_4")
      (libsource (lib "Schlib1") (part "WS2812_LED_4"))
    )
    (comp (ref "LED160")
      (value "WS2812_LED_4")
      (footprint "WS2812_LED_4")
      (libsource (lib "Schlib1") (part "WS2812_LED_4"))
    )
    (comp (ref "LED161")
      (value "WS2812_LED_4")
      (footprint "WS2812_LED_4")
      (libsource (lib "Schlib1") (part "WS2812_LED_4"))
    )
    (comp (ref "LED162")
      (value "WS2812_LED_4")
      (footprint "WS2812_LED_4")
      (libsource (lib "Schlib1") (part "WS2812_LED_4"))
    )
    (comp (ref "LED163")
      (value "WS2812_LED_4")
      (footprint "WS2812_LED_4")
      (libsource (lib "Schlib1") (part "WS2812_LED_4"))
    )
    (comp (ref "LED164")
      (value "WS2812_LED_4")
      (footprint "WS2812_LED_4")
      (libsource (lib "Schlib1") (part "WS2812_LED_4"))
    )
    (comp (ref "LED165")
      (value "WS2812_LED_4")
      (footprint "WS2812_LED_4")
      (libsource (lib "Schlib1") (part "WS2812_LED_4"))
    )
    (comp (ref "LED166")
      (value "WS2812_LED_4")
      (footprint "WS2812_LED_4")
      (libsource (lib "Schlib1") (part "WS2812_LED_4"))
    )
    (comp (ref "LED167")
      (value "WS2812_LED_4")
      (footprint "WS2812_LED_4")
      (libsource (lib "Schlib1") (part "WS2812_LED_4"))
    )
    (comp (ref "LED168")
      (value "WS2812_LED_4")
      (footprint "WS2812_LED_4")
      (libsource (lib "Schlib1") (part "WS2812_LED_4"))
    )
    (comp (ref "LED169")
      (value "WS2812_LED_4")
      (footprint "WS2812_LED_4")
      (libsource (lib "Schlib1") (part "WS2812_LED_4"))
    )
    (comp (ref "LED170")
      (value "WS2812_LED_4")
      (footprint "WS2812_LED_4")
      (libsource (lib "Schlib1") (part "WS2812_LED_4"))
    )
    (comp (ref "LED171")
      (value "WS2812_LED_4")
      (footprint "WS2812_LED_4")
      (libsource (lib "Schlib1") (part "WS2812_LED_4"))
    )
    (comp (ref "LED172")
      (value "WS2812_LED_4")
      (footprint "WS2812_LED_4")
      (libsource (lib "Schlib1") (part "WS2812_LED_4"))
    )
    (comp (ref "LED173")
      (value "WS2812_LED_4")
      (footprint "WS2812_LED_4")
      (libsource (lib "Schlib1") (part "WS2812_LED_4"))
    )
    (comp (ref "LED174")
      (value "WS2812_LED_4")
      (footprint "WS2812_LED_4")
      (libsource (lib "Schlib1") (part "WS2812_LED_4"))
    )
    (comp (ref "LED175")
      (value "WS2812_LED_4")
      (footprint "WS2812_LED_4")
      (libsource (lib "Schlib1") (part "WS2812_LED_4"))
    )
    (comp (ref "LED176")
      (value "WS2812_LED_4")
      (footprint "WS2812_LED_4")
      (libsource (lib "Schlib1") (part "WS2812_LED_4"))
    )
    (comp (ref "LED177")
      (value "WS2812_LED_4")
      (footprint "WS2812_LED_4")
      (libsource (lib "Schlib1") (part "WS2812_LED_4"))
    )
    (comp (ref "LED178")
      (value "WS2812_LED_4")
      (footprint "WS2812_LED_4")
      (libsource (lib "Schlib1") (part "WS2812_LED_4"))
    )
    (comp (ref "LED179")
      (value "WS2812_LED_4")
      (footprint "WS2812_LED_4")
      (libsource (lib "Schlib1") (part "WS2812_LED_4"))
    )
    (comp (ref "LED180")
      (value "WS2812_LED_4")
      (footprint "WS2812_LED_4")
      (libsource (lib "Schlib1") (part "WS2812_LED_4"))
    )
    (comp (ref "LED181")
      (value "WS2812_LED_4")
      (footprint "WS2812_LED_4")
      (libsource (lib "Schlib1") (part "WS2812_LED_4"))
    )
    (comp (ref "LED182")
      (value "WS2812_LED_4")
      (footprint "WS2812_LED_4")
      (libsource (lib "Schlib1") (part "WS2812_LED_4"))
    )
    (comp (ref "LED183")
      (value "WS2812_LED_4")
      (footprint "WS2812_LED_4")
      (libsource (lib "Schlib1") (part "WS2812_LED_4"))
    )
    (comp (ref "LED184")
      (value "WS2812_LED_4")
      (footprint "WS2812_LED_4")
      (libsource (lib "Schlib1") (part "WS2812_LED_4"))
    )
    (comp (ref "LED185")
      (value "WS2812_LED_4")
      (footprint "WS2812_LED_4")
      (libsource (lib "Schlib1") (part "WS2812_LED_4"))
    )
    (comp (ref "LED186")
      (value "WS2812_LED_4")
      (footprint "WS2812_LED_4")
      (libsource (lib "Schlib1") (part "WS2812_LED_4"))
    )
    (comp (ref "LED187")
      (value "WS2812_LED_4")
      (footprint "WS2812_LED_4")
      (libsource (lib "Schlib1") (part "WS2812_LED_4"))
    )
    (comp (ref "LED188")
      (value "WS2812_LED_4")
      (footprint "WS2812_LED_4")
      (libsource (lib "Schlib1") (part "WS2812_LED_4"))
    )
    (comp (ref "LED189")
      (value "WS2812_LED_4")
      (footprint "WS2812_LED_4")
      (libsource (lib "Schlib1") (part "WS2812_LED_4"))
    )
    (comp (ref "LED190")
      (value "WS2812_LED_4")
      (footprint "WS2812_LED_4")
      (libsource (lib "Schlib1") (part "WS2812_LED_4"))
    )
    (comp (ref "LED191")
      (value "WS2812_LED_4")
      (footprint "WS2812_LED_4")
      (libsource (lib "Schlib1") (part "WS2812_LED_4"))
    )
    (comp (ref "LED192")
      (value "WS2812_LED_4")
      (footprint "WS2812_LED_4")
      (libsource (lib "Schlib1") (part "WS2812_LED_4"))
    )
    (comp (ref "P1")
      (value "Header 3")
      (footprint "HDR1X3")
      (description "Header, 3-Pin")
      (fields (field (name "PUBLISHER") "Altium Limited"))
      (libsource (lib "Miscellaneous Connectors") (part "Header 3"))
    )
  )
  (nets
    (net (code "1") (name "+5") (class "Default")
      (node (ref "LED1") (pin "1") (pinfunction "VDD_1") (pintype "passive"))
      (node (ref "LED10") (pin "1") (pinfunction "VDD_1") (pintype "passive"))
      (node (ref "LED100") (pin "1") (pinfunction "VDD_1") (pintype "passive"))
      (node (ref "LED101") (pin "1") (pinfunction "VDD_1") (pintype "passive"))
      (node (ref "LED102") (pin "1") (pinfunction "VDD_1") (pintype "passive"))
      (node (ref "LED103") (pin "1") (pinfunction "VDD_1") (pintype "passive"))
      (node (ref "LED104") (pin "1") (pinfunction "VDD_1") (pintype "passive"))
      (node (ref "LED105") (pin "1") (pinfunction "VDD_1") (pintype "passive"))
      (node (ref "LED106") (pin "1") (pinfunction "VDD_1") (pintype "passive"))
      (node (ref "LED107") (pin "1") (pinfunction "VDD_1") (pintype "passive"))
      (node (ref "LED108") (pin "1") (pinfunction "VDD_1") (pintype "passive"))
      (node (ref "LED109") (pin "1") (pinfunction "VDD_1") (pintype "passive"))
      (node (ref "LED11") (pin "1") (pinfunction "VDD_1") (pintype "passive"))
      (node (ref "LED110") (pin "1") (pinfunction "VDD_1") (pintype "passive"))
      (node (ref "LED111") (pin "1") (pinfunction "VDD_1") (pintype "passive"))
      (node (ref "LED112") (pin "1") (pinfunction "VDD_1") (pintype "passive"))
      (node (ref "LED113") (pin "1") (pinfunction "VDD_1") (pintype "passive"))
      (node (ref "LED114") (pin "1") (pinfunction "VDD_1") (pintype "passive"))
      (node (ref "LED115") (pin "1") (pinfunction "VDD_1") (pintype "passive"))
      (node (ref "LED116") (pin "1") (pinfunction "VDD_1") (pintype "passive"))
      (node (ref "LED117") (pin "1") (pinfunction "VDD_1") (pintype "passive"))
      (node (ref "LED118") (pin "1") (pinfunction "VDD_1") (pintype "passive"))
      (node (ref "LED119") (pin "1") (pinfunction "VDD_1") (pintype "passive"))
      (node (ref "LED12") (pin "1") (pinfunction "VDD_1") (pintype "passive"))
      (node (ref "LED120") (pin "1") (pinfunction "VDD_1") (pintype "passive"))
      (node (ref "LED121") (pin "1") (pinfunction "VDD_1") (pintype "passive"))
      (node (ref "LED122") (pin "1") (pinfunction "VDD_1") (pintype "passive"))
      (node (ref "LED123") (pin "1") (pinfunction "VDD_1") (pintype "passive"))
      (node (ref "LED124") (pin "1") (pinfunction "VDD_1") (pintype "passive"))
      (node (ref "LED125") (pin "1") (pinfunction "VDD_1") (pintype "passive"))
      (node (ref "LED126") (pin "1") (pinfunction "VDD_1") (pintype "passive"))
      (node (ref "LED127") (pin "1") (pinfunction "VDD_1") (pintype "passive"))
      (node (ref "LED128") (pin "1") (pinfunction "VDD_1") (pintype "passive"))
      (node (ref "LED129") (pin "1") (pinfunction "VDD_1") (pintype "passive"))
      (node (ref "LED13") (pin "1") (pinfunction "VDD_1") (pintype "passive"))
      (node (ref "LED130") (pin "1") (pinfunction "VDD_1") (pintype "passive"))
      (node (ref "LED131") (pin "1") (pinfunction "VDD_1") (pintype "passive"))
      (node (ref "LED132") (pin "1") (pinfunction "VDD_1") (pintype "passive"))
      (node (ref "LED133") (pin "1") (pinfunction "VDD_1") (pintype "passive"))
      (node (ref "LED134") (pin "1") (pinfunction "VDD_1") (pintype "passive"))
      (node (ref "LED135") (pin "1") (pinfunction "VDD_1") (pintype "passive"))
      (node (ref "LED136") (pin "1") (pinfunction "VDD_1") (pintype "passive"))
      (node (ref "LED137") (pin "1") (pinfunction "VDD_1") (pintype "passive"))
      (node (ref "LED138") (pin "1") (pinfunction "VDD_1") (pintype "passive"))
      (node (ref "LED139") (pin "1") (pinfunction "VDD_1") (pintype "passive"))
      (node (ref "LED14") (pin "1") (pinfunction "VDD_1") (pintype "passive"))
      (node (ref "LED140") (pin "1") (pinfunction "VDD_1") (pintype "passive"))
      (node (ref "LED141") (pin "1") (pinfunction "VDD_1") (pintype "passive"))
      (node (ref "LED142") (pin "1") (pinfunction "VDD_1") (pintype "passive"))
      (node (ref "LED143") (pin "1") (pinfunction "VDD_1") (pintype "passive"))
      (node (ref "LED144") (pin "1") (pinfunction "VDD_1") (pintype "passive"))
      (node (ref "LED145") (pin "1") (pinfunction "VDD_1") (pintype "passive"))
      (node (ref "LED146") (pin "1") (pinfunction "VDD_1") (pintype "passive"))
      (node (ref "LED147") (pin "1") (pinfunction "VDD_1") (pintype "passive"))
      (node (ref "LED148") (pin "1") (pinfunction "VDD_1") (pintype "passive"))
      (node (ref "LED149") (pin "1") (pinfunction "VDD_1") (pintype "passive"))
      (node (ref "LED15") (pin "1") (pinfunction "VDD_1") (pintype "passive"))
      (node (ref "LED150") (pin "1") (pinfunction "VDD_1") (pintype "passive"))
      (node (ref "LED151") (pin "1") (pinfunction "VDD_1") (pintype "passive"))
      (node (ref "LED152") (pin "1") (pinfunction "VDD_1") (pintype "passive"))
      (node (ref "LED153") (pin "1") (pinfunction "VDD_1") (pintype "passive"))
      (node (ref "LED154") (pin "1") (pinfunction "VDD_1") (pintype "passive"))
      (node (ref "LED155") (pin "1") (pinfunction "VDD_1") (pintype "passive"))
      (node (ref "LED156") (pin "1") (pinfunction "VDD_1") (pintype "passive"))
      (node (ref "LED157") (pin "1") (pinfunction "VDD_1") (pintype "passive"))
      (node (ref "LED158") (pin "1") (pinfunction "VDD_1") (pintype "passive"))
      (node (ref "LED159") (pin "1") (pinfunction "VDD_1") (pintype "passive"))
      (node (ref "LED16") (pin "1") (pinfunction "VDD_1") (pintype "passive"))
      (node (ref "LED160") (pin "1") (pinfunction "VDD_1") (pintype "passive"))
      (node (ref "LED161") (pin "1") (pinfunction "VDD_1") (pintype "passive"))
      (node (ref "LED162") (pin "1") (pinfunction "VDD_1") (pintype "passive"))
      (node (ref "LED163") (pin "1") (pinfunction "VDD_1") (pintype "passive"))
      (node (ref "LED164") (pin "1") (pinfunction "VDD_1") (pintype "passive"))
      (node (ref "LED165") (pin "1") (pinfunction "VDD_1") (pintype "passive"))
      (node (ref "LED166") (pin "1") (pinfunction "VDD_1") (pintype "passive"))
      (node (ref "LED167") (pin "1") (pinfunction "VDD_1") (pintype "passive"))
      (node (ref "LED168") (pin "1") (pinfunction "VDD_1") (pintype "passive"))
      (node (ref "LED169") (pin "1") (pinfunction "VDD_1") (pintype "passive"))
      (node (ref "LED17") (pin "1") (pinfunction "VDD_1") (pintype "passive"))
      (node (ref "LED170") (pin "1") (pinfunction "VDD_1") (pintype "passive"))
      (node (ref "LED171") (pin "1") (pinfunction "VDD_1") (pintype "passive"))
      (node (ref "LED172") (pin "1") (pinfunction "VDD_1") (pintype "passive"))
      (node (ref "LED173") (pin "1") (pinfunction "VDD_1") (pintype "passive"))
      (node (ref "LED174") (pin "1") (pinfunction "VDD_1") (pintype "passive"))
      (node (ref "LED175") (pin "1") (pinfunction "VDD_1") (pintype "passive"))
      (node (ref "LED176") (pin "1") (pinfunction "VDD_1") (pintype "passive"))
      (node (ref "LED177") (pin "1") (pinfunction "VDD_1") (pintype "passive"))
      (node (ref "LED178") (pin "1") (pinfunction "VDD_1") (pintype "passive"))
      (node (ref "LED179") (pin "1") (pinfunction "VDD_1") (pintype "passive"))
      (node (ref "LED18") (pin "1") (pinfunction "VDD_1") (pintype "passive"))
      (node (ref "LED180") (pin "1") (pinfunction "VDD_1") (pintype "passive"))
      (node (ref "LED181") (pin "1") (pinfunction "VDD_1") (pintype "passive"))
      (node (ref "LED182") (pin "1") (pinfunction "VDD_1") (pintype "passive"))
      (node (ref "LED183") (pin "1") (pinfunction "VDD_1") (pintype "passive"))
      (node (ref "LED184") (pin "1") (pinfunction "VDD_1") (pintype "passive"))
      (node (ref "LED185") (pin "1") (pinfunction "VDD_1") (pintype "passive"))
      (node (ref "LED186") (pin "1") (pinfunction "VDD_1") (pintype "passive"))
      (node (ref "LED187") (pin "1") (pinfunction "VDD_1") (pintype "passive"))
      (node (ref "LED188") (pin "1") (pinfunction "VDD_1") (pintype "passive"))
      (node (ref "LED189") (pin "1") (pinfunction "VDD_1") (pintype "passive"))
      (node (ref "LED19") (pin "1") (pinfunction "VDD_1") (pintype "passive"))
      (node (ref "LED190") (pin "1") (pinfunction "VDD_1") (pintype "passive"))
      (node (ref "LED191") (pin "1") (pinfunction "VDD_1") (pintype "passive"))
      (node (ref "LED192") (pin "1") (pinfunction "VDD_1") (pintype "passive"))
      (node (ref "LED2") (pin "1") (pinfunction "VDD_1") (pintype "passive"))
      (node (ref "LED20") (pin "1") (pinfunction "VDD_1") (pintype "passive"))
      (node (ref "LED21") (pin "1") (pinfunction "VDD_1") (pintype "passive"))
      (node (ref "LED22") (pin "1") (pinfunction "VDD_1") (pintype "passive"))
      (node (ref "LED23") (pin "1") (pinfunction "VDD_1") (pintype "passive"))
      (node (ref "LED24") (pin "1") (pinfunction "VDD_1") (pintype "passive"))
      (node (ref "LED25") (pin "1") (pinfunction "VDD_1") (pintype "passive"))
      (node (ref "LED26") (pin "1") (pinfunction "VDD_1") (pintype "passive"))
      (node (ref "LED27") (pin "1") (pinfunction "VDD_1") (pintype "passive"))
      (node (ref "LED28") (pin "1") (pinfunction "VDD_1") (pintype "passive"))
      (node (ref "LED29") (pin "1") (pinfunction "VDD_1") (pintype "passive"))
      (node (ref "LED3") (pin "1") (pinfunction "VDD_1") (pintype "passive"))
      (node (ref "LED30") (pin "1") (pinfunction "VDD_1") (pintype "passive"))
      (node (ref "LED31") (pin "1") (pinfunction "VDD_1") (pintype "passive"))
      (node (ref "LED32") (pin "1") (pinfunction "VDD_1") (pintype "passive"))
      (node (ref "LED33") (pin "1") (pinfunction "VDD_1") (pintype "passive"))
      (node (ref "LED34") (pin "1") (pinfunction "VDD_1") (pintype "passive"))
      (node (ref "LED35") (pin "1") (pinfunction "VDD_1") (pintype "passive"))
      (node (ref "LED36") (pin "1") (pinfunction "VDD_1") (pintype "passive"))
      (node (ref "LED37") (pin "1") (pinfunction "VDD_1") (pintype "passive"))
      (node (ref "LED38") (pin "1") (pinfunction "VDD_1") (pintype "passive"))
      (node (ref "LED39") (pin "1") (pinfunction "VDD_1") (pintype "passive"))
      (node (ref "LED4") (pin "1") (pinfunction "VDD_1") (pintype "passive"))
      (node (ref "LED40") (pin "1") (pinfunction "VDD_1") (pintype "passive"))
      (node (ref "LED41") (pin "1") (pinfunction "VDD_1") (pintype "passive"))
      (node (ref "LED42") (pin "1") (pinfunction "VDD_1") (pintype "passive"))
      (node (ref "LED43") (pin "1") (pinfunction "VDD_1") (pintype "passive"))
      (node (ref "LED44") (pin "1") (pinfunction "VDD_1") (pintype "passive"))
      (node (ref "LED45") (pin "1") (pinfunction "VDD_1") (pintype "passive"))
      (node (ref "LED46") (pin "1") (pinfunction "VDD_1") (pintype "passive"))
      (node (ref "LED47") (pin "1") (pinfunction "VDD_1") (pintype "passive"))
      (node (ref "LED48") (pin "1") (pinfunction "VDD_1") (pintype "passive"))
      (node (ref "LED49") (pin "1") (pinfunction "VDD_1") (pintype "passive"))
      (node (ref "LED5") (pin "1") (pinfunction "VDD_1") (pintype "passive"))
      (node (ref "LED50") (pin "1") (pinfunction "VDD_1") (pintype "passive"))
      (node (ref "LED51") (pin "1") (pinfunction "VDD_1") (pintype "passive"))
      (node (ref "LED52") (pin "1") (pinfunction "VDD_1") (pintype "passive"))
      (node (ref "LED53") (pin "1") (pinfunction "VDD_1") (pintype "passive"))
      (node (ref "LED54") (pin "1") (pinfunction "VDD_1") (pintype "passive"))
      (node (ref "LED55") (pin "1") (pinfunction "VDD_1") (pintype "passive"))
      (node (ref "LED56") (pin "1") (pinfunction "VDD_1") (pintype "passive"))
      (node (ref "LED57") (pin "1") (pinfunction "VDD_1") (pintype "passive"))
      (node (ref "LED58") (pin "1") (pinfunction "VDD_1") (pintype "passive"))
      (node (ref "LED59") (pin "1") (pinfunction "VDD_1") (pintype "passive"))
      (node (ref "LED6") (pin "1") (pinfunction "VDD_1") (pintype "passive"))
      (node (ref "LED60") (pin "1") (pinfunction "VDD_1") (pintype "passive"))
      (node (ref "LED61") (pin "1") (pinfunction "VDD_1") (pintype "passive"))
      (node (ref "LED62") (pin "1") (pinfunction "VDD_1") (pintype "passive"))
      (node (ref "LED63") (pin "1") (pinfunction "VDD_1") (pintype "passive"))
      (node (ref "LED64") (pin "1") (pinfunction "VDD_1") (pintype "passive"))
      (node (ref "LED65") (pin "1") (pinfunction "VDD_1") (pintype "passive"))
      (node (ref "LED66") (pin "1") (pinfunction "VDD_1") (pintype "passive"))
      (node (ref "LED67") (pin "1") (pinfunction "VDD_1") (pintype "passive"))
      (node (ref "LED68") (pin "1") (pinfunction "VDD_1") (pintype "passive"))
      (node (ref "LED69") (pin "1") (pinfunction "VDD_1") (pintype "passive"))
      (node (ref "LED7") (pin "1") (pinfunction "VDD_1") (pintype "passive"))
      (node (ref "LED70") (pin "1") (pinfunction "VDD_1") (pintype "passive"))
      (node (ref "LED71") (pin "1") (pinfunction "VDD_1") (pintype "passive"))
      (node (ref "LED72") (pin "1") (pinfunction "VDD_1") (pintype "passive"))
      (node (ref "LED73") (pin "1") (pinfunction "VDD_1") (pintype "passive"))
      (node (ref "LED74") (pin "1") (pinfunction "VDD_1") (pintype "passive"))
      (node (ref "LED75") (pin "1") (pinfunction "VDD_1") (pintype "passive"))
      (node (ref "LED76") (pin "1") (pinfunction "VDD_1") (pintype "passive"))
      (node (ref "LED77") (pin "1") (pinfunction "VDD_1") (pintype "passive"))
      (node (ref "LED78") (pin "1") (pinfunction "VDD_1") (pintype "passive"))
      (node (ref "LED79") (pin "1") (pinfunction "VDD_1") (pintype "passive"))
      (node (ref "LED8") (pin "1") (pinfunction "VDD_1") (pintype "passive"))
      (node (ref "LED80") (pin "1") (pinfunction "VDD_1") (pintype "passive"))
      (node (ref "LED81") (pin "1") (pinfunction "VDD_1") (pintype "passive"))
      (node (ref "LED82") (pin "1") (pinfunction "VDD_1") (pintype "passive"))
      (node (ref "LED83") (pin "1") (pinfunction "VDD_1") (pintype "passive"))
      (node (ref "LED84") (pin "1") (pinfunction "VDD_1") (pintype "passive"))
      (node (ref "LED85") (pin "1") (pinfunction "VDD_1") (pintype "passive"))
      (node (ref "LED86") (pin "1") (pinfunction "VDD_1") (pintype "passive"))
      (node (ref "LED87") (pin "1") (pinfunction "VDD_1") (pintype "passive"))
      (node (ref "LED88") (pin "1") (pinfunction "VDD_1") (pintype "passive"))
      (node (ref "LED89") (pin "1") (pinfunction "VDD_1") (pintype "passive"))
      (node (ref "LED9") (pin "1") (pinfunction "VDD_1") (pintype "passive"))
      (node (ref "LED90") (pin "1") (pinfunction "VDD_1") (pintype "passive"))
      (node (ref "LED91") (pin "1") (pinfunction "VDD_1") (pintype "passive"))
      (node (ref "LED92") (pin "1") (pinfunction "VDD_1") (pintype "passive"))
      (node (ref "LED93") (pin "1") (pinfunction "VDD_1") (pintype "passive"))
      (node (ref "LED94") (pin "1") (pinfunction "VDD_1") (pintype "passive"))
      (node (ref "LED95") (pin "1") (pinfunction "VDD_1") (pintype "passive"))
      (node (ref "LED96") (pin "1") (pinfunction "VDD_1") (pintype "passive"))
      (node (ref "LED97") (pin "1") (pinfunction "VDD_1") (pintype "passive"))
      (node (ref "LED98") (pin "1") (pinfunction "VDD_1") (pintype "passive"))
      (node (ref "LED99") (pin "1") (pinfunction "VDD_1") (pintype "passive"))
      (node (ref "P1") (pin "1") (pinfunction "1_1") (pintype "passive"))
    )
    (net (code "2") (name "GND") (class "Default")
      (node (ref "C8") (pin "1") (pinfunction "1_1") (pintype "passive"))
      (node (ref "LED1") (pin "3") (pinfunction "VSS_3") (pintype "passive"))
      (node (ref "LED10") (pin "3") (pinfunction "VSS_3") (pintype "passive"))
      (node (ref "LED100") (pin "3") (pinfunction "VSS_3") (pintype "passive"))
      (node (ref "LED101") (pin "3") (pinfunction "VSS_3") (pintype "passive"))
      (node (ref "LED102") (pin "3") (pinfunction "VSS_3") (pintype "passive"))
      (node (ref "LED103") (pin "3") (pinfunction "VSS_3") (pintype "passive"))
      (node (ref "LED104") (pin "3") (pinfunction "VSS_3") (pintype "passive"))
      (node (ref "LED105") (pin "3") (pinfunction "VSS_3") (pintype "passive"))
      (node (ref "LED106") (pin "3") (pinfunction "VSS_3") (pintype "passive"))
      (node (ref "LED107") (pin "3") (pinfunction "VSS_3") (pintype "passive"))
      (node (ref "LED108") (pin "3") (pinfunction "VSS_3") (pintype "passive"))
      (node (ref "LED109") (pin "3") (pinfunction "VSS_3") (pintype "passive"))
      (node (ref "LED11") (pin "3") (pinfunction "VSS_3") (pintype "passive"))
      (node (ref "LED110") (pin "3") (pinfunction "VSS_3") (pintype "passive"))
      (node (ref "LED111") (pin "3") (pinfunction "VSS_3") (pintype "passive"))
      (node (ref "LED112") (pin "3") (pinfunction "VSS_3") (pintype "passive"))
      (node (ref "LED113") (pin "3") (pinfunction "VSS_3") (pintype "passive"))
      (node (ref "LED114") (pin "3") (pinfunction "VSS_3") (pintype "passive"))
      (node (ref "LED115") (pin "3") (pinfunction "VSS_3") (pintype "passive"))
      (node (ref "LED116") (pin "3") (pinfunction "VSS_3") (pintype "passive"))
      (node (ref "LED117") (pin "3") (pinfunction "VSS_3") (pintype "passive"))
      (node (ref "LED118") (pin "3") (pinfunction "VSS_3") (pintype "passive"))
      (node (ref "LED119") (pin "3") (pinfunction "VSS_3") (pintype "passive"))
      (node (ref "LED12") (pin "3") (pinfunction "VSS_3") (pintype "passive"))
      (node (ref "LED120") (pin "3") (pinfunction "VSS_3") (pintype "passive"))
      (node (ref "LED121") (pin "3") (pinfunction "VSS_3") (pintype "passive"))
      (node (ref "LED122") (pin "3") (pinfunction "VSS_3") (pintype "passive"))
      (node (ref "LED123") (pin "3") (pinfunction "VSS_3") (pintype "passive"))
      (node (ref "LED124") (pin "3") (pinfunction "VSS_3") (pintype "passive"))
      (node (ref "LED125") (pin "3") (pinfunction "VSS_3") (pintype "passive"))
      (node (ref "LED126") (pin "3") (pinfunction "VSS_3") (pintype "passive"))
      (node (ref "LED127") (pin "3") (pinfunction "VSS_3") (pintype "passive"))
      (node (ref "LED128") (pin "3") (pinfunction "VSS_3") (pintype "passive"))
      (node (ref "LED129") (pin "3") (pinfunction "VSS_3") (pintype "passive"))
      (node (ref "LED13") (pin "3") (pinfunction "VSS_3") (pintype "passive"))
      (node (ref "LED130") (pin "3") (pinfunction "VSS_3") (pintype "passive"))
      (node (ref "LED131") (pin "3") (pinfunction "VSS_3") (pintype "passive"))
      (node (ref "LED132") (pin "3") (pinfunction "VSS_3") (pintype "passive"))
      (node (ref "LED133") (pin "3") (pinfunction "VSS_3") (pintype "passive"))
      (node (ref "LED134") (pin "3") (pinfunction "VSS_3") (pintype "passive"))
      (node (ref "LED135") (pin "3") (pinfunction "VSS_3") (pintype "passive"))
      (node (ref "LED136") (pin "3") (pinfunction "VSS_3") (pintype "passive"))
      (node (ref "LED137") (pin "3") (pinfunction "VSS_3") (pintype "passive"))
      (node (ref "LED138") (pin "3") (pinfunction "VSS_3") (pintype "passive"))
      (node (ref "LED139") (pin "3") (pinfunction "VSS_3") (pintype "passive"))
      (node (ref "LED14") (pin "3") (pinfunction "VSS_3") (pintype "passive"))
      (node (ref "LED140") (pin "3") (pinfunction "VSS_3") (pintype "passive"))
      (node (ref "LED141") (pin "3") (pinfunction "VSS_3") (pintype "passive"))
      (node (ref "LED142") (pin "3") (pinfunction "VSS_3") (pintype "passive"))
      (node (ref "LED143") (pin "3") (pinfunction "VSS_3") (pintype "passive"))
      (node (ref "LED144") (pin "3") (pinfunction "VSS_3") (pintype "passive"))
      (node (ref "LED145") (pin "3") (pinfunction "VSS_3") (pintype "passive"))
      (node (ref "LED146") (pin "3") (pinfunction "VSS_3") (pintype "passive"))
      (node (ref "LED147") (pin "3") (pinfunction "VSS_3") (pintype "passive"))
      (node (ref "LED148") (pin "3") (pinfunction "VSS_3") (pintype "passive"))
      (node (ref "LED149") (pin "3") (pinfunction "VSS_3") (pintype "passive"))
      (node (ref "LED15") (pin "3") (pinfunction "VSS_3") (pintype "passive"))
      (node (ref "LED150") (pin "3") (pinfunction "VSS_3") (pintype "passive"))
      (node (ref "LED151") (pin "3") (pinfunction "VSS_3") (pintype "passive"))
      (node (ref "LED152") (pin "3") (pinfunction "VSS_3") (pintype "passive"))
      (node (ref "LED153") (pin "3") (pinfunction "VSS_3") (pintype "passive"))
      (node (ref "LED154") (pin "3") (pinfunction "VSS_3") (pintype "passive"))
      (node (ref "LED155") (pin "3") (pinfunction "VSS_3") (pintype "passive"))
      (node (ref "LED156") (pin "3") (pinfunction "VSS_3") (pintype "passive"))
      (node (ref "LED157") (pin "3") (pinfunction "VSS_3") (pintype "passive"))
      (node (ref "LED158") (pin "3") (pinfunction "VSS_3") (pintype "passive"))
      (node (ref "LED159") (pin "3") (pinfunction "VSS_3") (pintype "passive"))
      (node (ref "LED16") (pin "3") (pinfunction "VSS_3") (pintype "passive"))
      (node (ref "LED160") (pin "3") (pinfunction "VSS_3") (pintype "passive"))
      (node (ref "LED161") (pin "3") (pinfunction "VSS_3") (pintype "passive"))
      (node (ref "LED162") (pin "3") (pinfunction "VSS_3") (pintype "passive"))
      (node (ref "LED163") (pin "3") (pinfunction "VSS_3") (pintype "passive"))
      (node (ref "LED164") (pin "3") (pinfunction "VSS_3") (pintype "passive"))
      (node (ref "LED165") (pin "3") (pinfunction "VSS_3") (pintype "passive"))
      (node (ref "LED166") (pin "3") (pinfunction "VSS_3") (pintype "passive"))
      (node (ref "LED167") (pin "3") (pinfunction "VSS_3") (pintype "passive"))
      (node (ref "LED168") (pin "3") (pinfunction "VSS_3") (pintype "passive"))
      (node (ref "LED169") (pin "3") (pinfunction "VSS_3") (pintype "passive"))
      (node (ref "LED17") (pin "3") (pinfunction "VSS_3") (pintype "passive"))
      (node (ref "LED170") (pin "3") (pinfunction "VSS_3") (pintype "passive"))
      (node (ref "LED171") (pin "3") (pinfunction "VSS_3") (pintype "passive"))
      (node (ref "LED172") (pin "3") (pinfunction "VSS_3") (pintype "passive"))
      (node (ref "LED173") (pin "3") (pinfunction "VSS_3") (pintype "passive"))
      (node (ref "LED174") (pin "3") (pinfunction "VSS_3") (pintype "passive"))
      (node (ref "LED175") (pin "3") (pinfunction "VSS_3") (pintype "passive"))
      (node (ref "LED176") (pin "3") (pinfunction "VSS_3") (pintype "passive"))
      (node (ref "LED177") (pin "3") (pinfunction "VSS_3") (pintype "passive"))
      (node (ref "LED178") (pin "3") (pinfunction "VSS_3") (pintype "passive"))
      (node (ref "LED179") (pin "3") (pinfunction "VSS_3") (pintype "passive"))
      (node (ref "LED18") (pin "3") (pinfunction "VSS_3") (pintype "passive"))
      (node (ref "LED180") (pin "3") (pinfunction "VSS_3") (pintype "passive"))
      (node (ref "LED181") (pin "3") (pinfunction "VSS_3") (pintype "passive"))
      (node (ref "LED182") (pin "3") (pinfunction "VSS_3") (pintype "passive"))
      (node (ref "LED183") (pin "3") (pinfunction "VSS_3") (pintype "passive"))
      (node (ref "LED184") (pin "3") (pinfunction "VSS_3") (pintype "passive"))
      (node (ref "LED185") (pin "3") (pinfunction "VSS_3") (pintype "passive"))
      (node (ref "LED186") (pin "3") (pinfunction "VSS_3") (pintype "passive"))
      (node (ref "LED187") (pin "3") (pinfunction "VSS_3") (pintype "passive"))
      (node (ref "LED188") (pin "3") (pinfunction "VSS_3") (pintype "passive"))
      (node (ref "LED189") (pin "3") (pinfunction "VSS_3") (pintype "passive"))
      (node (ref "LED19") (pin "3") (pinfunction "VSS_3") (pintype "passive"))
      (node (ref "LED190") (pin "3") (pinfunction "VSS_3") (pintype "passive"))
      (node (ref "LED191") (pin "3") (pinfunction "VSS_3") (pintype "passive"))
      (node (ref "LED192") (pin "3") (pinfunction "VSS_3") (pintype "passive"))
      (node (ref "LED2") (pin "3") (pinfunction "VSS_3") (pintype "passive"))
      (node (ref "LED20") (pin "3") (pinfunction "VSS_3") (pintype "passive"))
      (node (ref "LED21") (pin "3") (pinfunction "VSS_3") (pintype "passive"))
      (node (ref "LED22") (pin "3") (pinfunction "VSS_3") (pintype "passive"))
      (node (ref "LED23") (pin "3") (pinfunction "VSS_3") (pintype "passive"))
      (node (ref "LED24") (pin "3") (pinfunction "VSS_3") (pintype "passive"))
      (node (ref "LED25") (pin "3") (pinfunction "VSS_3") (pintype "passive"))
      (node (ref "LED26") (pin "3") (pinfunction "VSS_3") (pintype "passive"))
      (node (ref "LED27") (pin "3") (pinfunction "VSS_3") (pintype "passive"))
      (node (ref "LED28") (pin "3") (pinfunction "VSS_3") (pintype "passive"))
      (node (ref "LED29") (pin "3") (pinfunction "VSS_3") (pintype "passive"))
      (node (ref "LED3") (pin "3") (pinfunction "VSS_3") (pintype "passive"))
      (node (ref "LED30") (pin "3") (pinfunction "VSS_3") (pintype "passive"))
      (node (ref "LED31") (pin "3") (pinfunction "VSS_3") (pintype "passive"))
      (node (ref "LED32") (pin "3") (pinfunction "VSS_3") (pintype "passive"))
      (node (ref "LED33") (pin "3") (pinfunction "VSS_3") (pintype "passive"))
      (node (ref "LED34") (pin "3") (pinfunction "VSS_3") (pintype "passive"))
      (node (ref "LED35") (pin "3") (pinfunction "VSS_3") (pintype "passive"))
      (node (ref "LED36") (pin "3") (pinfunction "VSS_3") (pintype "passive"))
      (node (ref "LED37") (pin "3") (pinfunction "VSS_3") (pintype "passive"))
      (node (ref "LED38") (pin "3") (pinfunction "VSS_3") (pintype "passive"))
      (node (ref "LED39") (pin "3") (pinfunction "VSS_3") (pintype "passive"))
      (node (ref "LED4") (pin "3") (pinfunction "VSS_3") (pintype "passive"))
      (node (ref "LED40") (pin "3") (pinfunction "VSS_3") (pintype "passive"))
      (node (ref "LED41") (pin "3") (pinfunction "VSS_3") (pintype "passive"))
      (node (ref "LED42") (pin "3") (pinfunction "VSS_3") (pintype "passive"))
      (node (ref "LED43") (pin "3") (pinfunction "VSS_3") (pintype "passive"))
      (node (ref "LED44") (pin "3") (pinfunction "VSS_3") (pintype "passive"))
      (node (ref "LED45") (pin "3") (pinfunction "VSS_3") (pintype "passive"))
      (node (ref "LED46") (pin "3") (pinfunction "VSS_3") (pintype "passive"))
      (node (ref "LED47") (pin "3") (pinfunction "VSS_3") (pintype "passive"))
      (node (ref "LED48") (pin "3") (pinfunction "VSS_3") (pintype "passive"))
      (node (ref "LED49") (pin "3") (pinfunction "VSS_3") (pintype "passive"))
      (node (ref "LED5") (pin "3") (pinfunction "VSS_3") (pintype "passive"))
      (node (ref "LED50") (pin "3") (pinfunction "VSS_3") (pintype "passive"))
      (node (ref "LED51") (pin "3") (pinfunction "VSS_3") (pintype "passive"))
      (node (ref "LED52") (pin "3") (pinfunction "VSS_3") (pintype "passive"))
      (node (ref "LED53") (pin "3") (pinfunction "VSS_3") (pintype "passive"))
      (node (ref "LED54") (pin "3") (pinfunction "VSS_3") (pintype "passive"))
      (node (ref "LED55") (pin "3") (pinfunction "VSS_3") (pintype "passive"))
      (node (ref "LED56") (pin "3") (pinfunction "VSS_3") (pintype "passive"))
      (node (ref "LED57") (pin "3") (pinfunction "VSS_3") (pintype "passive"))
      (node (ref "LED58") (pin "3") (pinfunction "VSS_3") (pintype "passive"))
      (node (ref "LED59") (pin "3") (pinfunction "VSS_3") (pintype "passive"))
      (node (ref "LED6") (pin "3") (pinfunction "VSS_3") (pintype "passive"))
      (node (ref "LED60") (pin "3") (pinfunction "VSS_3") (pintype "passive"))
      (node (ref "LED61") (pin "3") (pinfunction "VSS_3") (pintype "passive"))
      (node (ref "LED62") (pin "3") (pinfunction "VSS_3") (pintype "passive"))
      (node (ref "LED63") (pin "3") (pinfunction "VSS_3") (pintype "passive"))
      (node (ref "LED64") (pin "3") (pinfunction "VSS_3") (pintype "passive"))
      (node (ref "LED65") (pin "3") (pinfunction "VSS_3") (pintype "passive"))
      (node (ref "LED66") (pin "3") (pinfunction "VSS_3") (pintype "passive"))
      (node (ref "LED67") (pin "3") (pinfunction "VSS_3") (pintype "passive"))
      (node (ref "LED68") (pin "3") (pinfunction "VSS_3") (pintype "passive"))
      (node (ref "LED69") (pin "3") (pinfunction "VSS_3") (pintype "passive"))
      (node (ref "LED7") (pin "3") (pinfunction "VSS_3") (pintype "passive"))
      (node (ref "LED70") (pin "3") (pinfunction "VSS_3") (pintype "passive"))
      (node (ref "LED71") (pin "3") (pinfunction "VSS_3") (pintype "passive"))
      (node (ref "LED72") (pin "3") (pinfunction "VSS_3") (pintype "passive"))
      (node (ref "LED73") (pin "3") (pinfunction "VSS_3") (pintype "passive"))
      (node (ref "LED74") (pin "3") (pinfunction "VSS_3") (pintype "passive"))
      (node (ref "LED75") (pin "3") (pinfunction "VSS_3") (pintype "passive"))
      (node (ref "LED76") (pin "3") (pinfunction "VSS_3") (pintype "passive"))
      (node (ref "LED77") (pin "3") (pinfunction "VSS_3") (pintype "passive"))
      (node (ref "LED78") (pin "3") (pinfunction "VSS_3") (pintype "passive"))
      (node (ref "LED79") (pin "3") (pinfunction "VSS_3") (pintype "passive"))
      (node (ref "LED8") (pin "3") (pinfunction "VSS_3") (pintype "passive"))
      (node (ref "LED80") (pin "3") (pinfunction "VSS_3") (pintype "passive"))
      (node (ref "LED81") (pin "3") (pinfunction "VSS_3") (pintype "passive"))
      (node (ref "LED82") (pin "3") (pinfunction "VSS_3") (pintype "passive"))
      (node (ref "LED83") (pin "3") (pinfunction "VSS_3") (pintype "passive"))
      (node (ref "LED84") (pin "3") (pinfunction "VSS_3") (pintype "passive"))
      (node (ref "LED85") (pin "3") (pinfunction "VSS_3") (pintype "passive"))
      (node (ref "LED86") (pin "3") (pinfunction "VSS_3") (pintype "passive"))
      (node (ref "LED87") (pin "3") (pinfunction "VSS_3") (pintype "passive"))
      (node (ref "LED88") (pin "3") (pinfunction "VSS_3") (pintype "passive"))
      (node (ref "LED89") (pin "3") (pinfunction "VSS_3") (pintype "passive"))
      (node (ref "LED9") (pin "3") (pinfunction "VSS_3") (pintype "passive"))
      (node (ref "LED90") (pin "3") (pinfunction "VSS_3") (pintype "passive"))
      (node (ref "LED91") (pin "3") (pinfunction "VSS_3") (pintype "passive"))
      (node (ref "LED92") (pin "3") (pinfunction "VSS_3") (pintype "passive"))
      (node (ref "LED93") (pin "3") (pinfunction "VSS_3") (pintype "passive"))
      (node (ref "LED94") (pin "3") (pinfunction "VSS_3") (pintype "passive"))
      (node (ref "LED95") (pin "3") (pinfunction "VSS_3") (pintype "passive"))
      (node (ref "LED96") (pin "3") (pinfunction "VSS_3") (pintype "passive"))
      (node (ref "LED97") (pin "3") (pinfunction "VSS_3") (pintype "passive"))
      (node (ref "LED98") (pin "3") (pinfunction "VSS_3") (pintype "passive"))
      (node (ref "LED99") (pin "3") (pinfunction "VSS_3") (pintype "passive"))
      (node (ref "P1") (pin "3") (pinfunction "3_3") (pintype "passive"))
    )
    (net (code "3") (name "Net-(LED1-DIN)") (class "Default")
      (node (ref "LED1") (pin "4") (pinfunction "DIN_4") (pintype "passive"))
      (node (ref "LED2") (pin "2") (pinfunction "DOUT_2") (pintype "passive"))
    )
    (net (code "4") (name "Net-(LED1-DOUT)") (class "Default")
      (node (ref "LED1") (pin "2") (pinfunction "DOUT_2") (pintype "passive"))
      (node (ref "P1") (pin "2") (pinfunction "2_2") (pintype "passive"))
    )
    (net (code "5") (name "Net-(LED2-DIN)") (class "Default")
      (node (ref "LED2") (pin "4") (pinfunction "DIN_4") (pintype "passive"))
      (node (ref "LED3") (pin "2") (pinfunction "DOUT_2") (pintype "passive"))
    )
    (net (code "6") (name "Net-(LED3-DIN)") (class "Default")
      (node (ref "LED3") (pin "4") (pinfunction "DIN_4") (pintype "passive"))
      (node (ref "LED4") (pin "2") (pinfunction "DOUT_2") (pintype "passive"))
    )
    (net (code "7") (name "Net-(LED4-DIN)") (class "Default")
      (node (ref "LED4") (pin "4") (pinfunction "DIN_4") (pintype "passive"))
      (node (ref "LED5") (pin "2") (pinfunction "DOUT_2") (pintype "passive"))
    )
    (net (code "8") (name "Net-(LED5-DIN)") (class "Default")
      (node (ref "LED5") (pin "4") (pinfunction "DIN_4") (pintype "passive"))
      (node (ref "LED6") (pin "2") (pinfunction "DOUT_2") (pintype "passive"))
    )
    (net (code "9") (name "Net-(LED6-DIN)") (class "Default")
      (node (ref "LED6") (pin "4") (pinfunction "DIN_4") (pintype "passive"))
      (node (ref "LED7") (pin "2") (pinfunction "DOUT_2") (pintype "passive"))
    )
    (net (code "10") (name "Net-(LED7-DIN)") (class "Default")
      (node (ref "LED7") (pin "4") (pinfunction "DIN_4") (pintype "passive"))
      (node (ref "LED8") (pin "2") (pinfunction "DOUT_2") (pintype "passive"))
    )
    (net (code "11") (name "Net-(LED8-DIN)") (class "Default")
      (node (ref "LED8") (pin "4") (pinfunction "DIN_4") (pintype "passive"))
      (node (ref "LED9") (pin "2") (pinfunction "DOUT_2") (pintype "passive"))
    )
    (net (code "12") (name "Net-(LED10-DIN)") (class "Default")
      (node (ref "LED10") (pin "4") (pinfunction "DIN_4") (pintype "passive"))
      (node (ref "LED11") (pin "2") (pinfunction "DOUT_2") (pintype "passive"))
    )
    (net (code "13") (name "Net-(LED10-DOUT)") (class "Default")
      (node (ref "LED10") (pin "2") (pinfunction "DOUT_2") (pintype "passive"))
      (node (ref "LED9") (pin "4") (pinfunction "DIN_4") (pintype "passive"))
    )
    (net (code "14") (name "Net-(LED11-DIN)") (class "Default")
      (node (ref "LED11") (pin "4") (pinfunction "DIN_4") (pintype "passive"))
      (node (ref "LED12") (pin "2") (pinfunction "DOUT_2") (pintype "passive"))
    )
    (net (code "15") (name "Net-(LED12-DIN)") (class "Default")
      (node (ref "LED12") (pin "4") (pinfunction "DIN_4") (pintype "passive"))
      (node (ref "LED13") (pin "2") (pinfunction "DOUT_2") (pintype "passive"))
    )
    (net (code "16") (name "Net-(LED13-DIN)") (class "Default")
      (node (ref "LED13") (pin "4") (pinfunction "DIN_4") (pintype "passive"))
      (node (ref "LED14") (pin "2") (pinfunction "DOUT_2") (pintype "passive"))
    )
    (net (code "17") (name "Net-(LED14-DIN)") (class "Default")
      (node (ref "LED14") (pin "4") (pinfunction "DIN_4") (pintype "passive"))
      (node (ref "LED15") (pin "2") (pinfunction "DOUT_2") (pintype "passive"))
    )
    (net (code "18") (name "Net-(LED15-DIN)") (class "Default")
      (node (ref "LED15") (pin "4") (pinfunction "DIN_4") (pintype "passive"))
      (node (ref "LED16") (pin "2") (pinfunction "DOUT_2") (pintype "passive"))
    )
    (net (code "19") (name "Net-(LED16-DIN)") (class "Default")
      (node (ref "LED16") (pin "4") (pinfunction "DIN_4") (pintype "passive"))
      (node (ref "LED17") (pin "2") (pinfunction "DOUT_2") (pintype "passive"))
    )
    (net (code "20") (name "Net-(LED17-DIN)") (class "Default")
      (node (ref "LED17") (pin "4") (pinfunction "DIN_4") (pintype "passive"))
      (node (ref "LED18") (pin "2") (pinfunction "DOUT_2") (pintype "passive"))
    )
    (net (code "21") (name "Net-(LED18-DIN)") (class "Default")
      (node (ref "LED18") (pin "4") (pinfunction "DIN_4") (pintype "passive"))
      (node (ref "LED19") (pin "2") (pinfunction "DOUT_2") (pintype "passive"))
    )
    (net (code "22") (name "Net-(LED19-DIN)") (class "Default")
      (node (ref "LED19") (pin "4") (pinfunction "DIN_4") (pintype "passive"))
      (node (ref "LED20") (pin "2") (pinfunction "DOUT_2") (pintype "passive"))
    )
    (net (code "23") (name "Net-(LED20-DIN)") (class "Default")
      (node (ref "LED20") (pin "4") (pinfunction "DIN_4") (pintype "passive"))
      (node (ref "LED21") (pin "2") (pinfunction "DOUT_2") (pintype "passive"))
    )
    (net (code "24") (name "Net-(LED21-DIN)") (class "Default")
      (node (ref "LED21") (pin "4") (pinfunction "DIN_4") (pintype "passive"))
      (node (ref "LED22") (pin "2") (pinfunction "DOUT_2") (pintype "passive"))
    )
    (net (code "25") (name "Net-(LED22-DIN)") (class "Default")
      (node (ref "LED22") (pin "4") (pinfunction "DIN_4") (pintype "passive"))
      (node (ref "LED23") (pin "2") (pinfunction "DOUT_2") (pintype "passive"))
    )
    (net (code "26") (name "Net-(LED23-DIN)") (class "Default")
      (node (ref "LED23") (pin "4") (pinfunction "DIN_4") (pintype "passive"))
      (node (ref "LED24") (pin "2") (pinfunction "DOUT_2") (pintype "passive"))
    )
    (net (code "27") (name "Net-(LED24-DIN)") (class "Default")
      (node (ref "C1") (pin "2") (pinfunction "2_2") (pintype "passive"))
      (node (ref "LED24") (pin "4") (pinfunction "DIN_4") (pintype "passive"))
    )
    (net (code "28") (name "Net-(LED25-DIN)") (class "Default")
      (node (ref "LED25") (pin "4") (pinfunction "DIN_4") (pintype "passive"))
      (node (ref "LED26") (pin "2") (pinfunction "DOUT_2") (pintype "passive"))
    )
    (net (code "29") (name "Net-(LED25-DOUT)") (class "Default")
      (node (ref "C1") (pin "1") (pinfunction "1_1") (pintype "passive"))
      (node (ref "LED25") (pin "2") (pinfunction "DOUT_2") (pintype "passive"))
    )
    (net (code "30") (name "Net-(LED26-DIN)") (class "Default")
      (node (ref "LED26") (pin "4") (pinfunction "DIN_4") (pintype "passive"))
      (node (ref "LED27") (pin "2") (pinfunction "DOUT_2") (pintype "passive"))
    )
    (net (code "31") (name "Net-(LED27-DIN)") (class "Default")
      (node (ref "LED27") (pin "4") (pinfunction "DIN_4") (pintype "passive"))
      (node (ref "LED28") (pin "2") (pinfunction "DOUT_2") (pintype "passive"))
    )
    (net (code "32") (name "Net-(LED28-DIN)") (class "Default")
      (node (ref "LED28") (pin "4") (pinfunction "DIN_4") (pintype "passive"))
      (node (ref "LED29") (pin "2") (pinfunction "DOUT_2") (pintype "passive"))
    )
    (net (code "33") (name "Net-(LED29-DIN)") (class "Default")
      (node (ref "LED29") (pin "4") (pinfunction "DIN_4") (pintype "passive"))
      (node (ref "LED30") (pin "2") (pinfunction "DOUT_2") (pintype "passive"))
    )
    (net (code "34") (name "Net-(LED30-DIN)") (class "Default")
      (node (ref "LED30") (pin "4") (pinfunction "DIN_4") (pintype "passive"))
      (node (ref "LED31") (pin "2") (pinfunction "DOUT_2") (pintype "passive"))
    )
    (net (code "35") (name "Net-(LED31-DIN)") (class "Default")
      (node (ref "LED31") (pin "4") (pinfunction "DIN_4") (pintype "passive"))
      (node (ref "LED32") (pin "2") (pinfunction "DOUT_2") (pintype "passive"))
    )
    (net (code "36") (name "Net-(LED32-DIN)") (class "Default")
      (node (ref "LED32") (pin "4") (pinfunction "DIN_4") (pintype "passive"))
      (node (ref "LED33") (pin "2") (pinfunction "DOUT_2") (pintype "passive"))
    )
    (net (code "37") (name "Net-(LED33-DIN)") (class "Default")
      (node (ref "LED33") (pin "4") (pinfunction "DIN_4") (pintype "passive"))
      (node (ref "LED34") (pin "2") (pinfunction "DOUT_2") (pintype "passive"))
    )
    (net (code "38") (name "Net-(LED34-DIN)") (class "Default")
      (node (ref "LED34") (pin "4") (pinfunction "DIN_4") (pintype "passive"))
      (node (ref "LED35") (pin "2") (pinfunction "DOUT_2") (pintype "passive"))
    )
    (net (code "39") (name "Net-(LED35-DIN)") (class "Default")
      (node (ref "LED35") (pin "4") (pinfunction "DIN_4") (pintype "passive"))
      (node (ref "LED36") (pin "2") (pinfunction "DOUT_2") (pintype "passive"))
    )
    (net (code "40") (name "Net-(LED36-DIN)") (class "Default")
      (node (ref "LED36") (pin "4") (pinfunction "DIN_4") (pintype "passive"))
      (node (ref "LED37") (pin "2") (pinfunction "DOUT_2") (pintype "passive"))
    )
    (net (code "41") (name "Net-(LED37-DIN)") (class "Default")
      (node (ref "LED37") (pin "4") (pinfunction "DIN_4") (pintype "passive"))
      (node (ref "LED38") (pin "2") (pinfunction "DOUT_2") (pintype "passive"))
    )
    (net (code "42") (name "Net-(LED38-DIN)") (class "Default")
      (node (ref "LED38") (pin "4") (pinfunction "DIN_4") (pintype "passive"))
      (node (ref "LED39") (pin "2") (pinfunction "DOUT_2") (pintype "passive"))
    )
    (net (code "43") (name "Net-(LED39-DIN)") (class "Default")
      (node (ref "LED39") (pin "4") (pinfunction "DIN_4") (pintype "passive"))
      (node (ref "LED40") (pin "2") (pinfunction "DOUT_2") (pintype "passive"))
    )
    (net (code "44") (name "Net-(LED40-DIN)") (class "Default")
      (node (ref "LED40") (pin "4") (pinfunction "DIN_4") (pintype "passive"))
      (node (ref "LED41") (pin "2") (pinfunction "DOUT_2") (pintype "passive"))
    )
    (net (code "45") (name "Net-(LED41-DIN)") (class "Default")
      (node (ref "LED41") (pin "4") (pinfunction "DIN_4") (pintype "passive"))
      (node (ref "LED42") (pin "2") (pinfunction "DOUT_2") (pintype "passive"))
    )
    (net (code "46") (name "Net-(LED42-DIN)") (class "Default")
      (node (ref "LED42") (pin "4") (pinfunction "DIN_4") (pintype "passive"))
      (node (ref "LED43") (pin "2") (pinfunction "DOUT_2") (pintype "passive"))
    )
    (net (code "47") (name "Net-(LED43-DIN)") (class "Default")
      (node (ref "LED43") (pin "4") (pinfunction "DIN_4") (pintype "passive"))
      (node (ref "LED44") (pin "2") (pinfunction "DOUT_2") (pintype "passive"))
    )
    (net (code "48") (name "Net-(LED44-DIN)") (class "Default")
      (node (ref "LED44") (pin "4") (pinfunction "DIN_4") (pintype "passive"))
      (node (ref "LED45") (pin "2") (pinfunction "DOUT_2") (pintype "passive"))
    )
    (net (code "49") (name "Net-(LED45-DIN)") (class "Default")
      (node (ref "LED45") (pin "4") (pinfunction "DIN_4") (pintype "passive"))
      (node (ref "LED46") (pin "2") (pinfunction "DOUT_2") (pintype "passive"))
    )
    (net (code "50") (name "Net-(LED46-DIN)") (class "Default")
      (node (ref "LED46") (pin "4") (pinfunction "DIN_4") (pintype "passive"))
      (node (ref "LED47") (pin "2") (pinfunction "DOUT_2") (pintype "passive"))
    )
    (net (code "51") (name "Net-(LED47-DIN)") (class "Default")
      (node (ref "LED47") (pin "4") (pinfunction "DIN_4") (pintype "passive"))
      (node (ref "LED48") (pin "2") (pinfunction "DOUT_2") (pintype "passive"))
    )
    (net (code "52") (name "Net-(LED48-DIN)") (class "Default")
      (node (ref "C2") (pin "2") (pinfunction "2_2") (pintype "passive"))
      (node (ref "LED48") (pin "4") (pinfunction "DIN_4") (pintype "passive"))
    )
    (net (code "53") (name "Net-(LED49-DIN)") (class "Default")
      (node (ref "LED49") (pin "4") (pinfunction "DIN_4") (pintype "passive"))
      (node (ref "LED50") (pin "2") (pinfunction "DOUT_2") (pintype "passive"))
    )
    (net (code "54") (name "Net-(LED49-DOUT)") (class "Default")
      (node (ref "C2") (pin "1") (pinfunction "1_1") (pintype "passive"))
      (node (ref "LED49") (pin "2") (pinfunction "DOUT_2") (pintype "passive"))
    )
    (net (code "55") (name "Net-(LED50-DIN)") (class "Default")
      (node (ref "LED50") (pin "4") (pinfunction "DIN_4") (pintype "passive"))
      (node (ref "LED51") (pin "2") (pinfunction "DOUT_2") (pintype "passive"))
    )
    (net (code "56") (name "Net-(LED51-DIN)") (class "Default")
      (node (ref "LED51") (pin "4") (pinfunction "DIN_4") (pintype "passive"))
      (node (ref "LED52") (pin "2") (pinfunction "DOUT_2") (pintype "passive"))
    )
    (net (code "57") (name "Net-(LED52-DIN)") (class "Default")
      (node (ref "LED52") (pin "4") (pinfunction "DIN_4") (pintype "passive"))
      (node (ref "LED53") (pin "2") (pinfunction "DOUT_2") (pintype "passive"))
    )
    (net (code "58") (name "Net-(LED53-DIN)") (class "Default")
      (node (ref "LED53") (pin "4") (pinfunction "DIN_4") (pintype "passive"))
      (node (ref "LED54") (pin "2") (pinfunction "DOUT_2") (pintype "passive"))
    )
    (net (code "59") (name "Net-(LED54-DIN)") (class "Default")
      (node (ref "LED54") (pin "4") (pinfunction "DIN_4") (pintype "passive"))
      (node (ref "LED55") (pin "2") (pinfunction "DOUT_2") (pintype "passive"))
    )
    (net (code "60") (name "Net-(LED55-DIN)") (class "Default")
      (node (ref "LED55") (pin "4") (pinfunction "DIN_4") (pintype "passive"))
      (node (ref "LED56") (pin "2") (pinfunction "DOUT_2") (pintype "passive"))
    )
    (net (code "61") (name "Net-(LED56-DIN)") (class "Default")
      (node (ref "LED56") (pin "4") (pinfunction "DIN_4") (pintype "passive"))
      (node (ref "LED57") (pin "2") (pinfunction "DOUT_2") (pintype "passive"))
    )
    (net (code "62") (name "Net-(LED57-DIN)") (class "Default")
      (node (ref "LED57") (pin "4") (pinfunction "DIN_4") (pintype "passive"))
      (node (ref "LED58") (pin "2") (pinfunction "DOUT_2") (pintype "passive"))
    )
    (net (code "63") (name "Net-(LED58-DIN)") (class "Default")
      (node (ref "LED58") (pin "4") (pinfunction "DIN_4") (pintype "passive"))
      (node (ref "LED59") (pin "2") (pinfunction "DOUT_2") (pintype "passive"))
    )
    (net (code "64") (name "Net-(LED59-DIN)") (class "Default")
      (node (ref "LED59") (pin "4") (pinfunction "DIN_4") (pintype "passive"))
      (node (ref "LED60") (pin "2") (pinfunction "DOUT_2") (pintype "passive"))
    )
    (net (code "65") (name "Net-(LED60-DIN)") (class "Default")
      (node (ref "LED60") (pin "4") (pinfunction "DIN_4") (pintype "passive"))
      (node (ref "LED61") (pin "2") (pinfunction "DOUT_2") (pintype "passive"))
    )
    (net (code "66") (name "Net-(LED61-DIN)") (class "Default")
      (node (ref "LED61") (pin "4") (pinfunction "DIN_4") (pintype "passive"))
      (node (ref "LED62") (pin "2") (pinfunction "DOUT_2") (pintype "passive"))
    )
    (net (code "67") (name "Net-(LED62-DIN)") (class "Default")
      (node (ref "LED62") (pin "4") (pinfunction "DIN_4") (pintype "passive"))
      (node (ref "LED63") (pin "2") (pinfunction "DOUT_2") (pintype "passive"))
    )
    (net (code "68") (name "Net-(LED63-DIN)") (class "Default")
      (node (ref "LED63") (pin "4") (pinfunction "DIN_4") (pintype "passive"))
      (node (ref "LED64") (pin "2") (pinfunction "DOUT_2") (pintype "passive"))
    )
    (net (code "69") (name "Net-(LED64-DIN)") (class "Default")
      (node (ref "LED64") (pin "4") (pinfunction "DIN_4") (pintype "passive"))
      (node (ref "LED65") (pin "2") (pinfunction "DOUT_2") (pintype "passive"))
    )
    (net (code "70") (name "Net-(LED65-DIN)") (class "Default")
      (node (ref "LED65") (pin "4") (pinfunction "DIN_4") (pintype "passive"))
      (node (ref "LED66") (pin "2") (pinfunction "DOUT_2") (pintype "passive"))
    )
    (net (code "71") (name "Net-(LED66-DIN)") (class "Default")
      (node (ref "LED66") (pin "4") (pinfunction "DIN_4") (pintype "passive"))
      (node (ref "LED67") (pin "2") (pinfunction "DOUT_2") (pintype "passive"))
    )
    (net (code "72") (name "Net-(LED67-DIN)") (class "Default")
      (node (ref "LED67") (pin "4") (pinfunction "DIN_4") (pintype "passive"))
      (node (ref "LED68") (pin "2") (pinfunction "DOUT_2") (pintype "passive"))
    )
    (net (code "73") (name "Net-(LED68-DIN)") (class "Default")
      (node (ref "LED68") (pin "4") (pinfunction "DIN_4") (pintype "passive"))
      (node (ref "LED69") (pin "2") (pinfunction "DOUT_2") (pintype "passive"))
    )
    (net (code "74") (name "Net-(LED69-DIN)") (class "Default")
      (node (ref "LED69") (pin "4") (pinfunction "DIN_4") (pintype "passive"))
      (node (ref "LED70") (pin "2") (pinfunction "DOUT_2") (pintype "passive"))
    )
    (net (code "75") (name "Net-(LED70-DIN)") (class "Default")
      (node (ref "LED70") (pin "4") (pinfunction "DIN_4") (pintype "passive"))
      (node (ref "LED71") (pin "2") (pinfunction "DOUT_2") (pintype "passive"))
    )
    (net (code "76") (name "Net-(LED71-DIN)") (class "Default")
      (node (ref "LED71") (pin "4") (pinfunction "DIN_4") (pintype "passive"))
      (node (ref "LED72") (pin "2") (pinfunction "DOUT_2") (pintype "passive"))
    )
    (net (code "77") (name "Net-(LED72-DIN)") (class "Default")
      (node (ref "C3") (pin "2") (pinfunction "2_2") (pintype "passive"))
      (node (ref "LED72") (pin "4") (pinfunction "DIN_4") (pintype "passive"))
    )
    (net (code "78") (name "Net-(LED73-DIN)") (class "Default")
      (node (ref "LED73") (pin "4") (pinfunction "DIN_4") (pintype "passive"))
      (node (ref "LED74") (pin "2") (pinfunction "DOUT_2") (pintype "passive"))
    )
    (net (code "79") (name "Net-(LED73-DOUT)") (class "Default")
      (node (ref "C3") (pin "1") (pinfunction "1_1") (pintype "passive"))
      (node (ref "LED73") (pin "2") (pinfunction "DOUT_2") (pintype "passive"))
    )
    (net (code "80") (name "Net-(LED74-DIN)") (class "Default")
      (node (ref "LED74") (pin "4") (pinfunction "DIN_4") (pintype "passive"))
      (node (ref "LED75") (pin "2") (pinfunction "DOUT_2") (pintype "passive"))
    )
    (net (code "81") (name "Net-(LED75-DIN)") (class "Default")
      (node (ref "LED75") (pin "4") (pinfunction "DIN_4") (pintype "passive"))
      (node (ref "LED76") (pin "2") (pinfunction "DOUT_2") (pintype "passive"))
    )
    (net (code "82") (name "Net-(LED76-DIN)") (class "Default")
      (node (ref "LED76") (pin "4") (pinfunction "DIN_4") (pintype "passive"))
      (node (ref "LED77") (pin "2") (pinfunction "DOUT_2") (pintype "passive"))
    )
    (net (code "83") (name "Net-(LED77-DIN)") (class "Default")
      (node (ref "LED77") (pin "4") (pinfunction "DIN_4") (pintype "passive"))
      (node (ref "LED78") (pin "2") (pinfunction "DOUT_2") (pintype "passive"))
    )
    (net (code "84") (name "Net-(LED78-DIN)") (class "Default")
      (node (ref "LED78") (pin "4") (pinfunction "DIN_4") (pintype "passive"))
      (node (ref "LED79") (pin "2") (pinfunction "DOUT_2") (pintype "passive"))
    )
    (net (code "85") (name "Net-(LED79-DIN)") (class "Default")
      (node (ref "LED79") (pin "4") (pinfunction "DIN_4") (pintype "passive"))
      (node (ref "LED80") (pin "2") (pinfunction "DOUT_2") (pintype "passive"))
    )
    (net (code "86") (name "Net-(LED80-DIN)") (class "Default")
      (node (ref "LED80") (pin "4") (pinfunction "DIN_4") (pintype "passive"))
      (node (ref "LED81") (pin "2") (pinfunction "DOUT_2") (pintype "passive"))
    )
    (net (code "87") (name "Net-(LED81-DIN)") (class "Default")
      (node (ref "LED81") (pin "4") (pinfunction "DIN_4") (pintype "passive"))
      (node (ref "LED82") (pin "2") (pinfunction "DOUT_2") (pintype "passive"))
    )
    (net (code "88") (name "Net-(LED82-DIN)") (class "Default")
      (node (ref "LED82") (pin "4") (pinfunction "DIN_4") (pintype "passive"))
      (node (ref "LED83") (pin "2") (pinfunction "DOUT_2") (pintype "passive"))
    )
    (net (code "89") (name "Net-(LED83-DIN)") (class "Default")
      (node (ref "LED83") (pin "4") (pinfunction "DIN_4") (pintype "passive"))
      (node (ref "LED84") (pin "2") (pinfunction "DOUT_2") (pintype "passive"))
    )
    (net (code "90") (name "Net-(LED84-DIN)") (class "Default")
      (node (ref "LED84") (pin "4") (pinfunction "DIN_4") (pintype "passive"))
      (node (ref "LED85") (pin "2") (pinfunction "DOUT_2") (pintype "passive"))
    )
    (net (code "91") (name "Net-(LED85-DIN)") (class "Default")
      (node (ref "LED85") (pin "4") (pinfunction "DIN_4") (pintype "passive"))
      (node (ref "LED86") (pin "2") (pinfunction "DOUT_2") (pintype "passive"))
    )
    (net (code "92") (name "Net-(LED86-DIN)") (class "Default")
      (node (ref "LED86") (pin "4") (pinfunction "DIN_4") (pintype "passive"))
      (node (ref "LED87") (pin "2") (pinfunction "DOUT_2") (pintype "passive"))
    )
    (net (code "93") (name "Net-(LED87-DIN)") (class "Default")
      (node (ref "LED87") (pin "4") (pinfunction "DIN_4") (pintype "passive"))
      (node (ref "LED88") (pin "2") (pinfunction "DOUT_2") (pintype "passive"))
    )
    (net (code "94") (name "Net-(LED88-DIN)") (class "Default")
      (node (ref "LED88") (pin "4") (pinfunction "DIN_4") (pintype "passive"))
      (node (ref "LED89") (pin "2") (pinfunction "DOUT_2") (pintype "passive"))
    )
    (net (code "95") (name "Net-(LED89-DIN)") (class "Default")
      (node (ref "LED89") (pin "4") (pinfunction "DIN_4") (pintype "passive"))
      (node (ref "LED90") (pin "2") (pinfunction "DOUT_2") (pintype "passive"))
    )
    (net (code "96") (name "Net-(LED90-DIN)") (class "Default")
      (node (ref "LED90") (pin "4") (pinfunction "DIN_4") (pintype "passive"))
      (node (ref "LED91") (pin "2") (pinfunction "DOUT_2") (pintype "passive"))
    )
    (net (code "97") (name "Net-(LED91-DIN)") (class "Default")
      (node (ref "LED91") (pin "4") (pinfunction "DIN_4") (pintype "passive"))
      (node (ref "LED92") (pin "2") (pinfunction "DOUT_2") (pintype "passive"))
    )
    (net (code "98") (name "Net-(LED92-DIN)") (class "Default")
      (node (ref "LED92") (pin "4") (pinfunction "DIN_4") (pintype "passive"))
      (node (ref "LED93") (pin "2") (pinfunction "DOUT_2") (pintype "passive"))
    )
    (net (code "99") (name "Net-(LED93-DIN)") (class "Default")
      (node (ref "LED93") (pin "4") (pinfunction "DIN_4") (pintype "passive"))
      (node (ref "LED94") (pin "2") (pinfunction "DOUT_2") (pintype "passive"))
    )
    (net (code "100") (name "Net-(LED94-DIN)") (class "Default")
      (node (ref "LED94") (pin "4") (pinfunction "DIN_4") (pintype "passive"))
      (node (ref "LED95") (pin "2") (pinfunction "DOUT_2") (pintype "passive"))
    )
    (net (code "101") (name "Net-(LED95-DIN)") (class "Default")
      (node (ref "LED95") (pin "4") (pinfunction "DIN_4") (pintype "passive"))
      (node (ref "LED96") (pin "2") (pinfunction "DOUT_2") (pintype "passive"))
    )
    (net (code "102") (name "Net-(LED96-DIN)") (class "Default")
      (node (ref "C4") (pin "2") (pinfunction "2_2") (pintype "passive"))
      (node (ref "LED96") (pin "4") (pinfunction "DIN_4") (pintype "passive"))
    )
    (net (code "103") (name "Net-(LED97-DIN)") (class "Default")
      (node (ref "LED97") (pin "4") (pinfunction "DIN_4") (pintype "passive"))
      (node (ref "LED98") (pin "2") (pinfunction "DOUT_2") (pintype "passive"))
    )
    (net (code "104") (name "Net-(LED97-DOUT)") (class "Default")
      (node (ref "C4") (pin "1") (pinfunction "1_1") (pintype "passive"))
      (node (ref "LED97") (pin "2") (pinfunction "DOUT_2") (pintype "passive"))
    )
    (net (code "105") (name "Net-(LED98-DIN)") (class "Default")
      (node (ref "LED98") (pin "4") (pinfunction "DIN_4") (pintype "passive"))
      (node (ref "LED99") (pin "2") (pinfunction "DOUT_2") (pintype "passive"))
    )
    (net (code "106") (name "Net-(LED100-DIN)") (class "Default")
      (node (ref "LED100") (pin "4") (pinfunction "DIN_4") (pintype "passive"))
      (node (ref "LED101") (pin "2") (pinfunction "DOUT_2") (pintype "passive"))
    )
    (net (code "107") (name "Net-(LED100-DOUT)") (class "Default")
      (node (ref "LED100") (pin "2") (pinfunction "DOUT_2") (pintype "passive"))
      (node (ref "LED99") (pin "4") (pinfunction "DIN_4") (pintype "passive"))
    )
    (net (code "108") (name "Net-(LED101-DIN)") (class "Default")
      (node (ref "LED101") (pin "4") (pinfunction "DIN_4") (pintype "passive"))
      (node (ref "LED102") (pin "2") (pinfunction "DOUT_2") (pintype "passive"))
    )
    (net (code "109") (name "Net-(LED102-DIN)") (class "Default")
      (node (ref "LED102") (pin "4") (pinfunction "DIN_4") (pintype "passive"))
      (node (ref "LED103") (pin "2") (pinfunction "DOUT_2") (pintype "passive"))
    )
    (net (code "110") (name "Net-(LED103-DIN)") (class "Default")
      (node (ref "LED103") (pin "4") (pinfunction "DIN_4") (pintype "passive"))
      (node (ref "LED104") (pin "2") (pinfunction "DOUT_2") (pintype "passive"))
    )
    (net (code "111") (name "Net-(LED104-DIN)") (class "Default")
      (node (ref "LED104") (pin "4") (pinfunction "DIN_4") (pintype "passive"))
      (node (ref "LED105") (pin "2") (pinfunction "DOUT_2") (pintype "passive"))
    )
    (net (code "112") (name "Net-(LED105-DIN)") (class "Default")
      (node (ref "LED105") (pin "4") (pinfunction "DIN_4") (pintype "passive"))
      (node (ref "LED106") (pin "2") (pinfunction "DOUT_2") (pintype "passive"))
    )
    (net (code "113") (name "Net-(LED106-DIN)") (class "Default")
      (node (ref "LED106") (pin "4") (pinfunction "DIN_4") (pintype "passive"))
      (node (ref "LED107") (pin "2") (pinfunction "DOUT_2") (pintype "passive"))
    )
    (net (code "114") (name "Net-(LED107-DIN)") (class "Default")
      (node (ref "LED107") (pin "4") (pinfunction "DIN_4") (pintype "passive"))
      (node (ref "LED108") (pin "2") (pinfunction "DOUT_2") (pintype "passive"))
    )
    (net (code "115") (name "Net-(LED108-DIN)") (class "Default")
      (node (ref "LED108") (pin "4") (pinfunction "DIN_4") (pintype "passive"))
      (node (ref "LED109") (pin "2") (pinfunction "DOUT_2") (pintype "passive"))
    )
    (net (code "116") (name "Net-(LED109-DIN)") (class "Default")
      (node (ref "LED109") (pin "4") (pinfunction "DIN_4") (pintype "passive"))
      (node (ref "LED110") (pin "2") (pinfunction "DOUT_2") (pintype "passive"))
    )
    (net (code "117") (name "Net-(LED110-DIN)") (class "Default")
      (node (ref "LED110") (pin "4") (pinfunction "DIN_4") (pintype "passive"))
      (node (ref "LED111") (pin "2") (pinfunction "DOUT_2") (pintype "passive"))
    )
    (net (code "118") (name "Net-(LED111-DIN)") (class "Default")
      (node (ref "LED111") (pin "4") (pinfunction "DIN_4") (pintype "passive"))
      (node (ref "LED112") (pin "2") (pinfunction "DOUT_2") (pintype "passive"))
    )
    (net (code "119") (name "Net-(LED112-DIN)") (class "Default")
      (node (ref "LED112") (pin "4") (pinfunction "DIN_4") (pintype "passive"))
      (node (ref "LED113") (pin "2") (pinfunction "DOUT_2") (pintype "passive"))
    )
    (net (code "120") (name "Net-(LED113-DIN)") (class "Default")
      (node (ref "LED113") (pin "4") (pinfunction "DIN_4") (pintype "passive"))
      (node (ref "LED114") (pin "2") (pinfunction "DOUT_2") (pintype "passive"))
    )
    (net (code "121") (name "Net-(LED114-DIN)") (class "Default")
      (node (ref "LED114") (pin "4") (pinfunction "DIN_4") (pintype "passive"))
      (node (ref "LED115") (pin "2") (pinfunction "DOUT_2") (pintype "passive"))
    )
    (net (code "122") (name "Net-(LED115-DIN)") (class "Default")
      (node (ref "LED115") (pin "4") (pinfunction "DIN_4") (pintype "passive"))
      (node (ref "LED116") (pin "2") (pinfunction "DOUT_2") (pintype "passive"))
    )
    (net (code "123") (name "Net-(LED116-DIN)") (class "Default")
      (node (ref "LED116") (pin "4") (pinfunction "DIN_4") (pintype "passive"))
      (node (ref "LED117") (pin "2") (pinfunction "DOUT_2") (pintype "passive"))
    )
    (net (code "124") (name "Net-(LED117-DIN)") (class "Default")
      (node (ref "LED117") (pin "4") (pinfunction "DIN_4") (pintype "passive"))
      (node (ref "LED118") (pin "2") (pinfunction "DOUT_2") (pintype "passive"))
    )
    (net (code "125") (name "Net-(LED118-DIN)") (class "Default")
      (node (ref "LED118") (pin "4") (pinfunction "DIN_4") (pintype "passive"))
      (node (ref "LED119") (pin "2") (pinfunction "DOUT_2") (pintype "passive"))
    )
    (net (code "126") (name "Net-(LED119-DIN)") (class "Default")
      (node (ref "LED119") (pin "4") (pinfunction "DIN_4") (pintype "passive"))
      (node (ref "LED120") (pin "2") (pinfunction "DOUT_2") (pintype "passive"))
    )
    (net (code "127") (name "Net-(LED120-DIN)") (class "Default")
      (node (ref "C5") (pin "2") (pinfunction "2_2") (pintype "passive"))
      (node (ref "LED120") (pin "4") (pinfunction "DIN_4") (pintype "passive"))
    )
    (net (code "128") (name "Net-(LED121-DIN)") (class "Default")
      (node (ref "LED121") (pin "4") (pinfunction "DIN_4") (pintype "passive"))
      (node (ref "LED122") (pin "2") (pinfunction "DOUT_2") (pintype "passive"))
    )
    (net (code "129") (name "Net-(LED121-DOUT)") (class "Default")
      (node (ref "C5") (pin "1") (pinfunction "1_1") (pintype "passive"))
      (node (ref "LED121") (pin "2") (pinfunction "DOUT_2") (pintype "passive"))
    )
    (net (code "130") (name "Net-(LED122-DIN)") (class "Default")
      (node (ref "LED122") (pin "4") (pinfunction "DIN_4") (pintype "passive"))
      (node (ref "LED123") (pin "2") (pinfunction "DOUT_2") (pintype "passive"))
    )
    (net (code "131") (name "Net-(LED123-DIN)") (class "Default")
      (node (ref "LED123") (pin "4") (pinfunction "DIN_4") (pintype "passive"))
      (node (ref "LED124") (pin "2") (pinfunction "DOUT_2") (pintype "passive"))
    )
    (net (code "132") (name "Net-(LED124-DIN)") (class "Default")
      (node (ref "LED124") (pin "4") (pinfunction "DIN_4") (pintype "passive"))
      (node (ref "LED125") (pin "2") (pinfunction "DOUT_2") (pintype "passive"))
    )
    (net (code "133") (name "Net-(LED125-DIN)") (class "Default")
      (node (ref "LED125") (pin "4") (pinfunction "DIN_4") (pintype "passive"))
      (node (ref "LED126") (pin "2") (pinfunction "DOUT_2") (pintype "passive"))
    )
    (net (code "134") (name "Net-(LED126-DIN)") (class "Default")
      (node (ref "LED126") (pin "4") (pinfunction "DIN_4") (pintype "passive"))
      (node (ref "LED127") (pin "2") (pinfunction "DOUT_2") (pintype "passive"))
    )
    (net (code "135") (name "Net-(LED127-DIN)") (class "Default")
      (node (ref "LED127") (pin "4") (pinfunction "DIN_4") (pintype "passive"))
      (node (ref "LED128") (pin "2") (pinfunction "DOUT_2") (pintype "passive"))
    )
    (net (code "136") (name "Net-(LED128-DIN)") (class "Default")
      (node (ref "LED128") (pin "4") (pinfunction "DIN_4") (pintype "passive"))
      (node (ref "LED129") (pin "2") (pinfunction "DOUT_2") (pintype "passive"))
    )
    (net (code "137") (name "Net-(LED129-DIN)") (class "Default")
      (node (ref "LED129") (pin "4") (pinfunction "DIN_4") (pintype "passive"))
      (node (ref "LED130") (pin "2") (pinfunction "DOUT_2") (pintype "passive"))
    )
    (net (code "138") (name "Net-(LED130-DIN)") (class "Default")
      (node (ref "LED130") (pin "4") (pinfunction "DIN_4") (pintype "passive"))
      (node (ref "LED131") (pin "2") (pinfunction "DOUT_2") (pintype "passive"))
    )
    (net (code "139") (name "Net-(LED131-DIN)") (class "Default")
      (node (ref "LED131") (pin "4") (pinfunction "DIN_4") (pintype "passive"))
      (node (ref "LED132") (pin "2") (pinfunction "DOUT_2") (pintype "passive"))
    )
    (net (code "140") (name "Net-(LED132-DIN)") (class "Default")
      (node (ref "LED132") (pin "4") (pinfunction "DIN_4") (pintype "passive"))
      (node (ref "LED133") (pin "2") (pinfunction "DOUT_2") (pintype "passive"))
    )
    (net (code "141") (name "Net-(LED133-DIN)") (class "Default")
      (node (ref "LED133") (pin "4") (pinfunction "DIN_4") (pintype "passive"))
      (node (ref "LED134") (pin "2") (pinfunction "DOUT_2") (pintype "passive"))
    )
    (net (code "142") (name "Net-(LED134-DIN)") (class "Default")
      (node (ref "LED134") (pin "4") (pinfunction "DIN_4") (pintype "passive"))
      (node (ref "LED135") (pin "2") (pinfunction "DOUT_2") (pintype "passive"))
    )
    (net (code "143") (name "Net-(LED135-DIN)") (class "Default")
      (node (ref "LED135") (pin "4") (pinfunction "DIN_4") (pintype "passive"))
      (node (ref "LED136") (pin "2") (pinfunction "DOUT_2") (pintype "passive"))
    )
    (net (code "144") (name "Net-(LED136-DIN)") (class "Default")
      (node (ref "LED136") (pin "4") (pinfunction "DIN_4") (pintype "passive"))
      (node (ref "LED137") (pin "2") (pinfunction "DOUT_2") (pintype "passive"))
    )
    (net (code "145") (name "Net-(LED137-DIN)") (class "Default")
      (node (ref "LED137") (pin "4") (pinfunction "DIN_4") (pintype "passive"))
      (node (ref "LED138") (pin "2") (pinfunction "DOUT_2") (pintype "passive"))
    )
    (net (code "146") (name "Net-(LED138-DIN)") (class "Default")
      (node (ref "LED138") (pin "4") (pinfunction "DIN_4") (pintype "passive"))
      (node (ref "LED139") (pin "2") (pinfunction "DOUT_2") (pintype "passive"))
    )
    (net (code "147") (name "Net-(LED139-DIN)") (class "Default")
      (node (ref "LED139") (pin "4") (pinfunction "DIN_4") (pintype "passive"))
      (node (ref "LED140") (pin "2") (pinfunction "DOUT_2") (pintype "passive"))
    )
    (net (code "148") (name "Net-(LED140-DIN)") (class "Default")
      (node (ref "LED140") (pin "4") (pinfunction "DIN_4") (pintype "passive"))
      (node (ref "LED141") (pin "2") (pinfunction "DOUT_2") (pintype "passive"))
    )
    (net (code "149") (name "Net-(LED141-DIN)") (class "Default")
      (node (ref "LED141") (pin "4") (pinfunction "DIN_4") (pintype "passive"))
      (node (ref "LED142") (pin "2") (pinfunction "DOUT_2") (pintype "passive"))
    )
    (net (code "150") (name "Net-(LED142-DIN)") (class "Default")
      (node (ref "LED142") (pin "4") (pinfunction "DIN_4") (pintype "passive"))
      (node (ref "LED143") (pin "2") (pinfunction "DOUT_2") (pintype "passive"))
    )
    (net (code "151") (name "Net-(LED143-DIN)") (class "Default")
      (node (ref "LED143") (pin "4") (pinfunction "DIN_4") (pintype "passive"))
      (node (ref "LED144") (pin "2") (pinfunction "DOUT_2") (pintype "passive"))
    )
    (net (code "152") (name "Net-(LED144-DIN)") (class "Default")
      (node (ref "C6") (pin "2") (pinfunction "2_2") (pintype "passive"))
      (node (ref "LED144") (pin "4") (pinfunction "DIN_4") (pintype "passive"))
    )
    (net (code "153") (name "Net-(LED145-DIN)") (class "Default")
      (node (ref "LED145") (pin "4") (pinfunction "DIN_4") (pintype "passive"))
      (node (ref "LED146") (pin "2") (pinfunction "DOUT_2") (pintype "passive"))
    )
    (net (code "154") (name "Net-(LED145-DOUT)") (class "Default")
      (node (ref "C6") (pin "1") (pinfunction "1_1") (pintype "passive"))
      (node (ref "LED145") (pin "2") (pinfunction "DOUT_2") (pintype "passive"))
    )
    (net (code "155") (name "Net-(LED146-DIN)") (class "Default")
      (node (ref "LED146") (pin "4") (pinfunction "DIN_4") (pintype "passive"))
      (node (ref "LED147") (pin "2") (pinfunction "DOUT_2") (pintype "passive"))
    )
    (net (code "156") (name "Net-(LED147-DIN)") (class "Default")
      (node (ref "LED147") (pin "4") (pinfunction "DIN_4") (pintype "passive"))
      (node (ref "LED148") (pin "2") (pinfunction "DOUT_2") (pintype "passive"))
    )
    (net (code "157") (name "Net-(LED148-DIN)") (class "Default")
      (node (ref "LED148") (pin "4") (pinfunction "DIN_4") (pintype "passive"))
      (node (ref "LED149") (pin "2") (pinfunction "DOUT_2") (pintype "passive"))
    )
    (net (code "158") (name "Net-(LED149-DIN)") (class "Default")
      (node (ref "LED149") (pin "4") (pinfunction "DIN_4") (pintype "passive"))
      (node (ref "LED150") (pin "2") (pinfunction "DOUT_2") (pintype "passive"))
    )
    (net (code "159") (name "Net-(LED150-DIN)") (class "Default")
      (node (ref "LED150") (pin "4") (pinfunction "DIN_4") (pintype "passive"))
      (node (ref "LED151") (pin "2") (pinfunction "DOUT_2") (pintype "passive"))
    )
    (net (code "160") (name "Net-(LED151-DIN)") (class "Default")
      (node (ref "LED151") (pin "4") (pinfunction "DIN_4") (pintype "passive"))
      (node (ref "LED152") (pin "2") (pinfunction "DOUT_2") (pintype "passive"))
    )
    (net (code "161") (name "Net-(LED152-DIN)") (class "Default")
      (node (ref "LED152") (pin "4") (pinfunction "DIN_4") (pintype "passive"))
      (node (ref "LED153") (pin "2") (pinfunction "DOUT_2") (pintype "passive"))
    )
    (net (code "162") (name "Net-(LED153-DIN)") (class "Default")
      (node (ref "LED153") (pin "4") (pinfunction "DIN_4") (pintype "passive"))
      (node (ref "LED154") (pin "2") (pinfunction "DOUT_2") (pintype "passive"))
    )
    (net (code "163") (name "Net-(LED154-DIN)") (class "Default")
      (node (ref "LED154") (pin "4") (pinfunction "DIN_4") (pintype "passive"))
      (node (ref "LED155") (pin "2") (pinfunction "DOUT_2") (pintype "passive"))
    )
    (net (code "164") (name "Net-(LED155-DIN)") (class "Default")
      (node (ref "LED155") (pin "4") (pinfunction "DIN_4") (pintype "passive"))
      (node (ref "LED156") (pin "2") (pinfunction "DOUT_2") (pintype "passive"))
    )
    (net (code "165") (name "Net-(LED156-DIN)") (class "Default")
      (node (ref "LED156") (pin "4") (pinfunction "DIN_4") (pintype "passive"))
      (node (ref "LED157") (pin "2") (pinfunction "DOUT_2") (pintype "passive"))
    )
    (net (code "166") (name "Net-(LED157-DIN)") (class "Default")
      (node (ref "LED157") (pin "4") (pinfunction "DIN_4") (pintype "passive"))
      (node (ref "LED158") (pin "2") (pinfunction "DOUT_2") (pintype "passive"))
    )
    (net (code "167") (name "Net-(LED158-DIN)") (class "Default")
      (node (ref "LED158") (pin "4") (pinfunction "DIN_4") (pintype "passive"))
      (node (ref "LED159") (pin "2") (pinfunction "DOUT_2") (pintype "passive"))
    )
    (net (code "168") (name "Net-(LED159-DIN)") (class "Default")
      (node (ref "LED159") (pin "4") (pinfunction "DIN_4") (pintype "passive"))
      (node (ref "LED160") (pin "2") (pinfunction "DOUT_2") (pintype "passive"))
    )
    (net (code "169") (name "Net-(LED160-DIN)") (class "Default")
      (node (ref "LED160") (pin "4") (pinfunction "DIN_4") (pintype "passive"))
      (node (ref "LED161") (pin "2") (pinfunction "DOUT_2") (pintype "passive"))
    )
    (net (code "170") (name "Net-(LED161-DIN)") (class "Default")
      (node (ref "LED161") (pin "4") (pinfunction "DIN_4") (pintype "passive"))
      (node (ref "LED162") (pin "2") (pinfunction "DOUT_2") (pintype "passive"))
    )
    (net (code "171") (name "Net-(LED162-DIN)") (class "Default")
      (node (ref "LED162") (pin "4") (pinfunction "DIN_4") (pintype "passive"))
      (node (ref "LED163") (pin "2") (pinfunction "DOUT_2") (pintype "passive"))
    )
    (net (code "172") (name "Net-(LED163-DIN)") (class "Default")
      (node (ref "LED163") (pin "4") (pinfunction "DIN_4") (pintype "passive"))
      (node (ref "LED164") (pin "2") (pinfunction "DOUT_2") (pintype "passive"))
    )
    (net (code "173") (name "Net-(LED164-DIN)") (class "Default")
      (node (ref "LED164") (pin "4") (pinfunction "DIN_4") (pintype "passive"))
      (node (ref "LED165") (pin "2") (pinfunction "DOUT_2") (pintype "passive"))
    )
    (net (code "174") (name "Net-(LED165-DIN)") (class "Default")
      (node (ref "LED165") (pin "4") (pinfunction "DIN_4") (pintype "passive"))
      (node (ref "LED166") (pin "2") (pinfunction "DOUT_2") (pintype "passive"))
    )
    (net (code "175") (name "Net-(LED166-DIN)") (class "Default")
      (node (ref "LED166") (pin "4") (pinfunction "DIN_4") (pintype "passive"))
      (node (ref "LED167") (pin "2") (pinfunction "DOUT_2") (pintype "passive"))
    )
    (net (code "176") (name "Net-(LED167-DIN)") (class "Default")
      (node (ref "LED167") (pin "4") (pinfunction "DIN_4") (pintype "passive"))
      (node (ref "LED168") (pin "2") (pinfunction "DOUT_2") (pintype "passive"))
    )
    (net (code "177") (name "Net-(LED168-DIN)") (class "Default")
      (node (ref "C7") (pin "2") (pinfunction "2_2") (pintype "passive"))
      (node (ref "LED168") (pin "4") (pinfunction "DIN_4") (pintype "passive"))
    )
    (net (code "178") (name "Net-(LED169-DIN)") (class "Default")
      (node (ref "LED169") (pin "4") (pinfunction "DIN_4") (pintype "passive"))
      (node (ref "LED170") (pin "2") (pinfunction "DOUT_2") (pintype "passive"))
    )
    (net (code "179") (name "Net-(LED169-DOUT)") (class "Default")
      (node (ref "C7") (pin "1") (pinfunction "1_1") (pintype "passive"))
      (node (ref "LED169") (pin "2") (pinfunction "DOUT_2") (pintype "passive"))
    )
    (net (code "180") (name "Net-(LED170-DIN)") (class "Default")
      (node (ref "LED170") (pin "4") (pinfunction "DIN_4") (pintype "passive"))
      (node (ref "LED171") (pin "2") (pinfunction "DOUT_2") (pintype "passive"))
    )
    (net (code "181") (name "Net-(LED171-DIN)") (class "Default")
      (node (ref "LED171") (pin "4") (pinfunction "DIN_4") (pintype "passive"))
      (node (ref "LED172") (pin "2") (pinfunction "DOUT_2") (pintype "passive"))
    )
    (net (code "182") (name "Net-(LED172-DIN)") (class "Default")
      (node (ref "LED172") (pin "4") (pinfunction "DIN_4") (pintype "passive"))
      (node (ref "LED173") (pin "2") (pinfunction "DOUT_2") (pintype "passive"))
    )
    (net (code "183") (name "Net-(LED173-DIN)") (class "Default")
      (node (ref "LED173") (pin "4") (pinfunction "DIN_4") (pintype "passive"))
      (node (ref "LED174") (pin "2") (pinfunction "DOUT_2") (pintype "passive"))
    )
    (net (code "184") (name "Net-(LED174-DIN)") (class "Default")
      (node (ref "LED174") (pin "4") (pinfunction "DIN_4") (pintype "passive"))
      (node (ref "LED175") (pin "2") (pinfunction "DOUT_2") (pintype "passive"))
    )
    (net (code "185") (name "Net-(LED175-DIN)") (class "Default")
      (node (ref "LED175") (pin "4") (pinfunction "DIN_4") (pintype "passive"))
      (node (ref "LED176") (pin "2") (pinfunction "DOUT_2") (pintype "passive"))
    )
    (net (code "186") (name "Net-(LED176-DIN)") (class "Default")
      (node (ref "LED176") (pin "4") (pinfunction "DIN_4") (pintype "passive"))
      (node (ref "LED177") (pin "2") (pinfunction "DOUT_2") (pintype "passive"))
    )
    (net (code "187") (name "Net-(LED177-DIN)") (class "Default")
      (node (ref "LED177") (pin "4") (pinfunction "DIN_4") (pintype "passive"))
      (node (ref "LED178") (pin "2") (pinfunction "DOUT_2") (pintype "passive"))
    )
    (net (code "188") (name "Net-(LED178-DIN)") (class "Default")
      (node (ref "LED178") (pin "4") (pinfunction "DIN_4") (pintype "passive"))
      (node (ref "LED179") (pin "2") (pinfunction "DOUT_2") (pintype "passive"))
    )
    (net (code "189") (name "Net-(LED179-DIN)") (class "Default")
      (node (ref "LED179") (pin "4") (pinfunction "DIN_4") (pintype "passive"))
      (node (ref "LED180") (pin "2") (pinfunction "DOUT_2") (pintype "passive"))
    )
    (net (code "190") (name "Net-(LED180-DIN)") (class "Default")
      (node (ref "LED180") (pin "4") (pinfunction "DIN_4") (pintype "passive"))
      (node (ref "LED181") (pin "2") (pinfunction "DOUT_2") (pintype "passive"))
    )
    (net (code "191") (name "Net-(LED181-DIN)") (class "Default")
      (node (ref "LED181") (pin "4") (pinfunction "DIN_4") (pintype "passive"))
      (node (ref "LED182") (pin "2") (pinfunction "DOUT_2") (pintype "passive"))
    )
    (net (code "192") (name "Net-(LED182-DIN)") (class "Default")
      (node (ref "LED182") (pin "4") (pinfunction "DIN_4") (pintype "passive"))
      (node (ref "LED183") (pin "2") (pinfunction "DOUT_2") (pintype "passive"))
    )
    (net (code "193") (name "Net-(LED183-DIN)") (class "Default")
      (node (ref "LED183") (pin "4") (pinfunction "DIN_4") (pintype "passive"))
      (node (ref "LED184") (pin "2") (pinfunction "DOUT_2") (pintype "passive"))
    )
    (net (code "194") (name "Net-(LED184-DIN)") (class "Default")
      (node (ref "LED184") (pin "4") (pinfunction "DIN_4") (pintype "passive"))
      (node (ref "LED185") (pin "2") (pinfunction "DOUT_2") (pintype "passive"))
    )
    (net (code "195") (name "Net-(LED185-DIN)") (class "Default")
      (node (ref "LED185") (pin "4") (pinfunction "DIN_4") (pintype "passive"))
      (node (ref "LED186") (pin "2") (pinfunction "DOUT_2") (pintype "passive"))
    )
    (net (code "196") (name "Net-(LED186-DIN)") (class "Default")
      (node (ref "LED186") (pin "4") (pinfunction "DIN_4") (pintype "passive"))
      (node (ref "LED187") (pin "2") (pinfunction "DOUT_2") (pintype "passive"))
    )
    (net (code "197") (name "Net-(LED187-DIN)") (class "Default")
      (node (ref "LED187") (pin "4") (pinfunction "DIN_4") (pintype "passive"))
      (node (ref "LED188") (pin "2") (pinfunction "DOUT_2") (pintype "passive"))
    )
    (net (code "198") (name "Net-(LED188-DIN)") (class "Default")
      (node (ref "LED188") (pin "4") (pinfunction "DIN_4") (pintype "passive"))
      (node (ref "LED189") (pin "2") (pinfunction "DOUT_2") (pintype "passive"))
    )
    (net (code "199") (name "Net-(LED189-DIN)") (class "Default")
      (node (ref "LED189") (pin "4") (pinfunction "DIN_4") (pintype "passive"))
      (node (ref "LED190") (pin "2") (pinfunction "DOUT_2") (pintype "passive"))
    )
    (net (code "200") (name "Net-(LED190-DIN)") (class "Default")
      (node (ref "LED190") (pin "4") (pinfunction "DIN_4") (pintype "passive"))
      (node (ref "LED191") (pin "2") (pinfunction "DOUT_2") (pintype "passive"))
    )
    (net (code "201") (name "Net-(LED191-DIN)") (class "Default")
      (node (ref "LED191") (pin "4") (pinfunction "DIN_4") (pintype "passive"))
      (node (ref "LED192") (pin "2") (pinfunction "DOUT_2") (pintype "passive"))
    )
    (net (code "202") (name "Net-(LED192-DIN)") (class "Default")
      (node (ref "C8") (pin "2") (pinfunction "2_2") (pintype "passive"))
      (node (ref "LED192") (pin "4") (pinfunction "DIN_4") (pintype "passive"))
    )
  )
)
